# ProPrj___2025-12-12.net
KiCad netlist of a schematic drawn in EasyEDA Pro
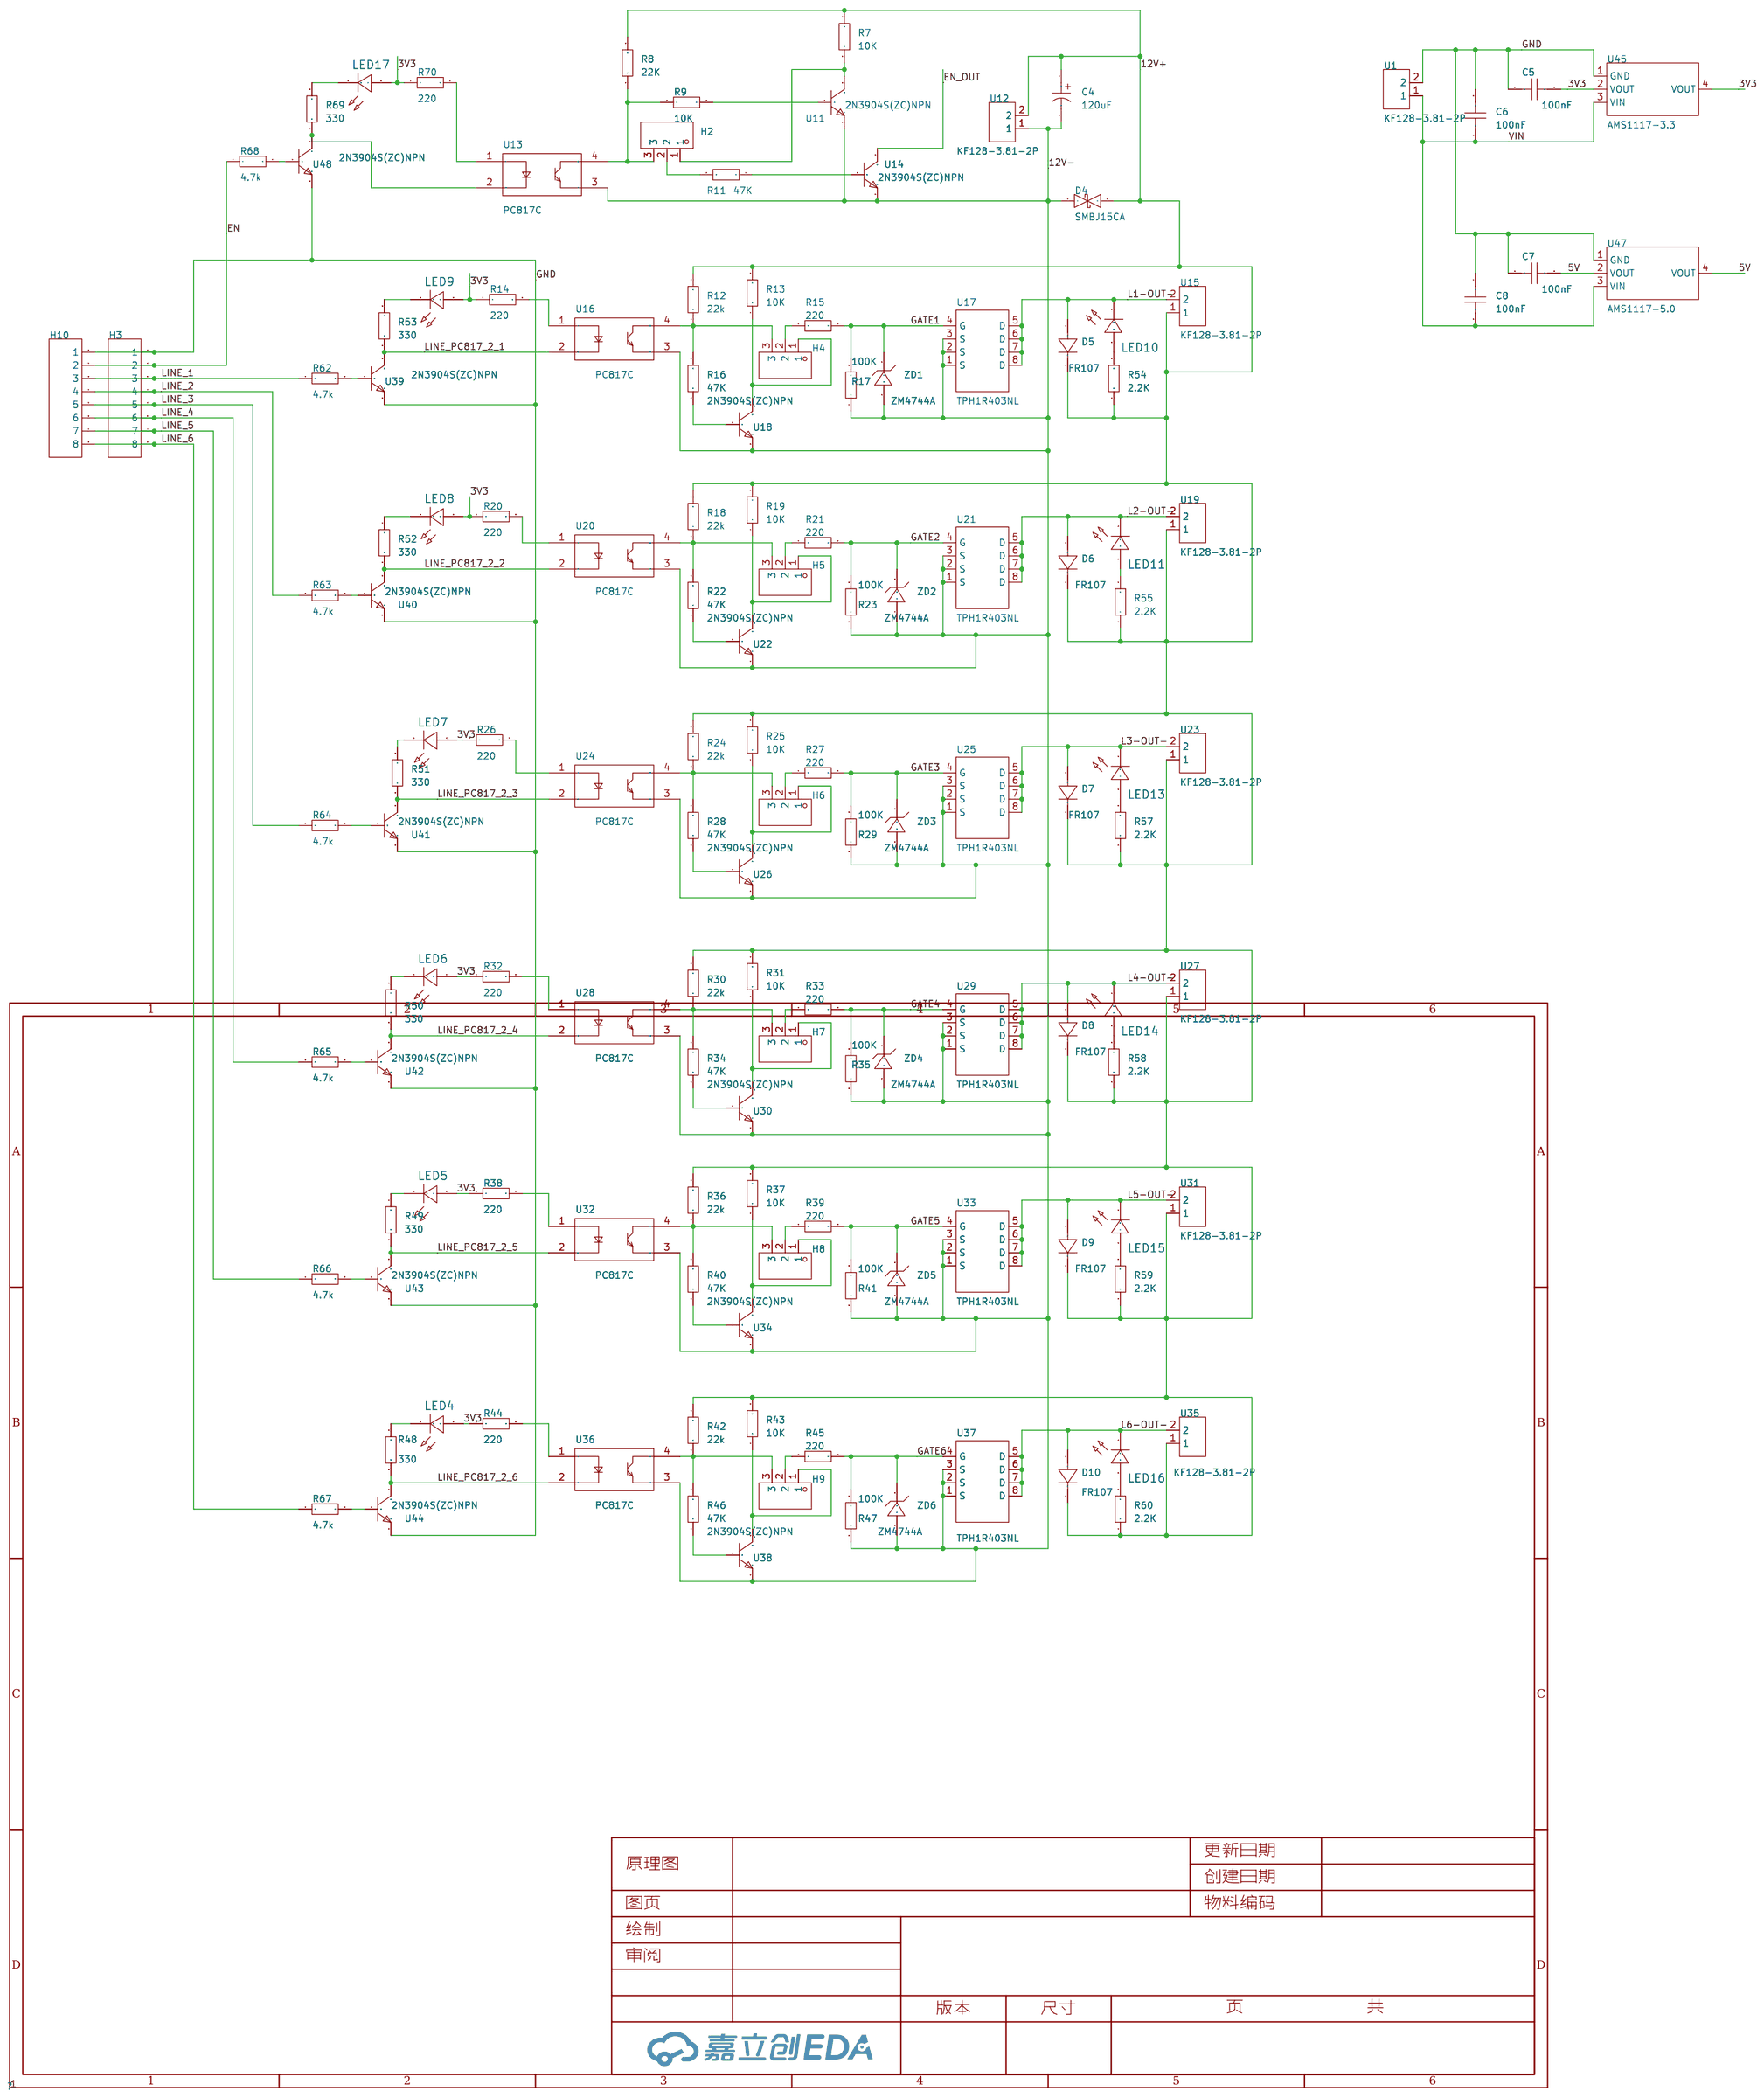
[diagram p0: 光耦隔离输出]
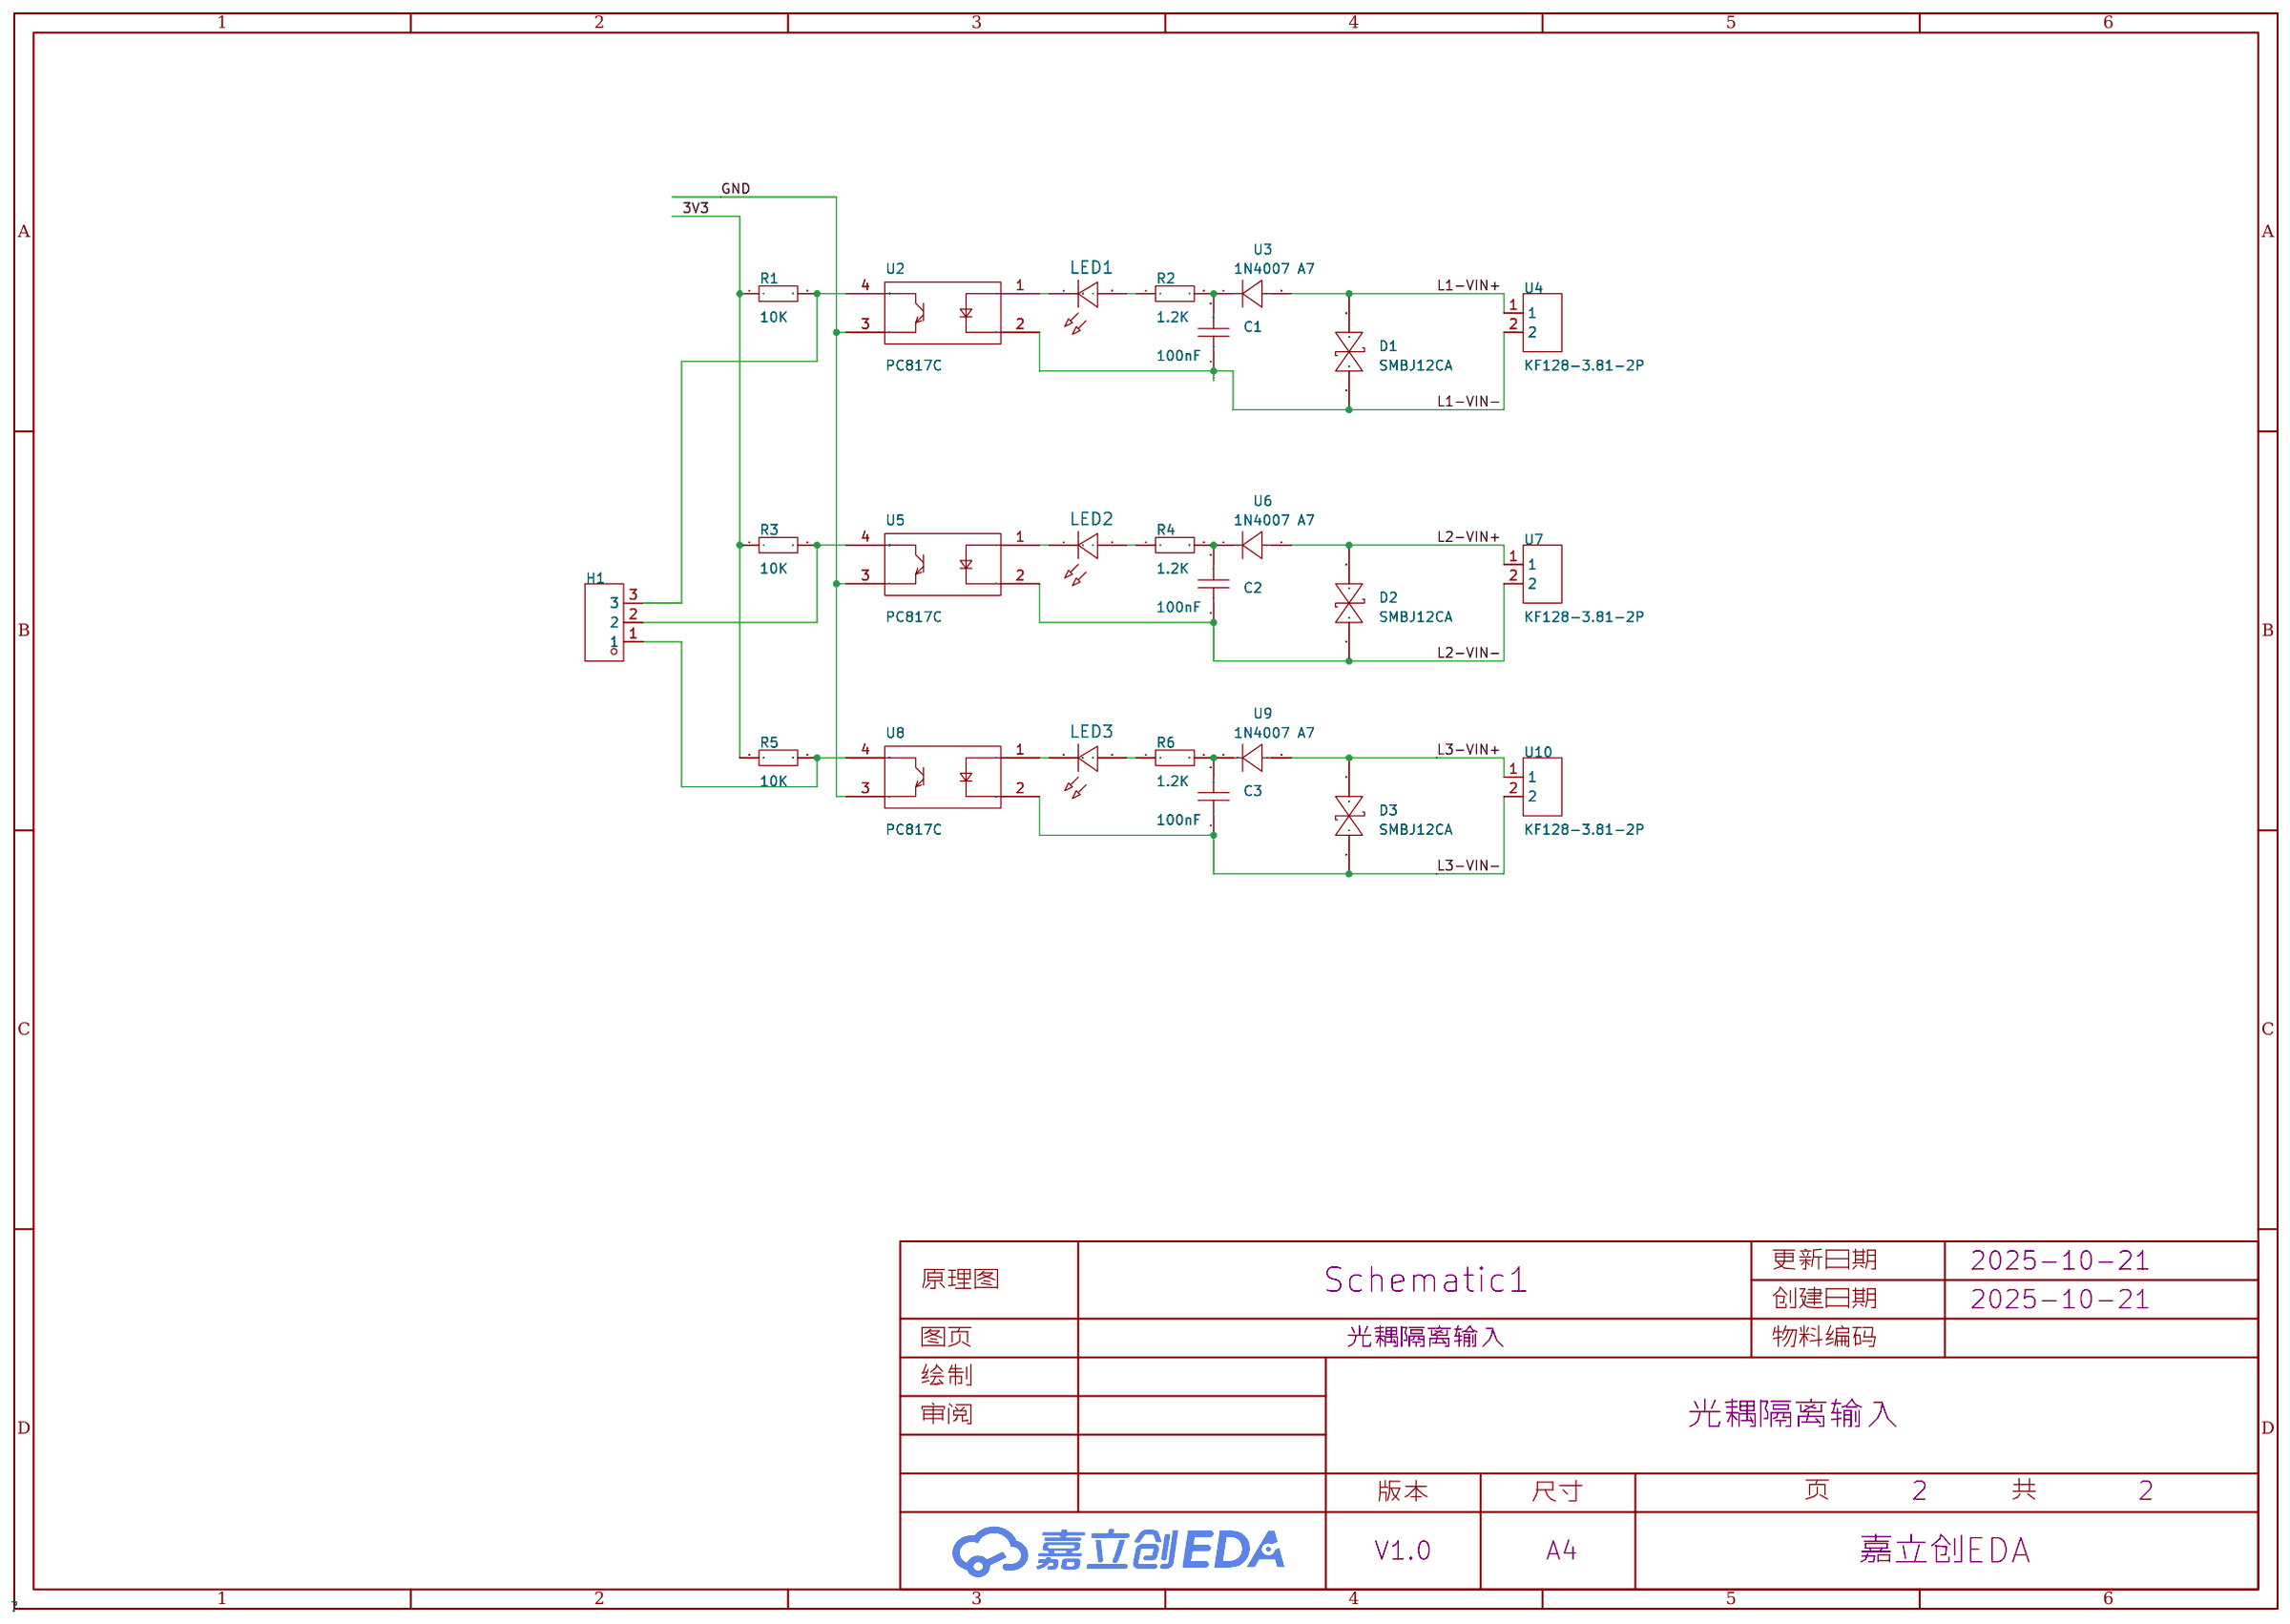
[diagram p1: 光耦隔离输入]

(export (version "E")
  (design (tool "Eeschema 10.0.6"))
  (components
    (comp (ref "C4")
      (value "120uF")
      (footprint "easyedapro:CAP-TH_BD6.3-P2.50-D0.5-FD")
      (description "容值:120uF;精度:±20%;额定电压:35V;纹波电流:550mA@100kHz;等效串联电阻(ESR):150mΩ@100kHz;")
      (fields
        (field (name "Manufacturer Part") "DHG035M127E090S1AA")
        (field (name "Manufacturer") "KNSCHA(科尼盛)")
      )
      (libsource (lib "easyedapro") (part "DHG035M127E090S1AA"))
    )
    (comp (ref "C5")
      (value "100nF")
      (footprint "easyedapro:C0603")
      (libsource (lib "easyedapro") (part "CapAcitance"))
    )
    (comp (ref "C6")
      (value "100nF")
      (footprint "easyedapro:C0603")
      (libsource (lib "easyedapro") (part "CapAcitance"))
    )
    (comp (ref "C7")
      (value "100nF")
      (footprint "easyedapro:C0603")
      (libsource (lib "easyedapro") (part "CapAcitance"))
    )
    (comp (ref "C8")
      (value "100nF")
      (footprint "easyedapro:C0603")
      (libsource (lib "easyedapro") (part "CapAcitance"))
    )
    (comp (ref "D4")
      (value "SMBJ15CA")
      (footprint "easyedapro:SMB_L4.6-W3.6-LS5.3-BI")
      (description "反向截止电压(Vrwm):15V;钳位电压:24.4V;峰值脉冲电流(Ipp):24.6A;击穿电压:16.7V;")
      (fields (field (name "Manufacturer") "JJW(捷捷微)"))
      (libsource (lib "easyedapro") (part "SMBJ15CA_C330064"))
    )
    (comp (ref "D5")
      (value "FR107")
      (footprint "easyedapro:SOD-123_L2.8-W1.8-LS3.7-RD")
      (description "二极管配置:-;正向压降(Vf):1.3V@1A;直流反向耐压(Vr):1kV;整流电流:1A;反向恢复时间(Trr):500ns;")
      (fields (field (name "Manufacturer") "JSMSEMI(杰盛微)"))
      (libsource (lib "easyedapro") (part "FR107_C963379"))
    )
    (comp (ref "D6")
      (value "FR107")
      (footprint "easyedapro:SOD-123_L2.8-W1.8-LS3.7-RD")
      (description "二极管配置:-;正向压降(Vf):1.3V@1A;直流反向耐压(Vr):1kV;整流电流:1A;反向恢复时间(Trr):500ns;")
      (fields (field (name "Manufacturer") "JSMSEMI(杰盛微)"))
      (libsource (lib "easyedapro") (part "FR107_C963379"))
    )
    (comp (ref "D7")
      (value "FR107")
      (footprint "easyedapro:SOD-123_L2.8-W1.8-LS3.7-RD")
      (description "二极管配置:-;正向压降(Vf):1.3V@1A;直流反向耐压(Vr):1kV;整流电流:1A;反向恢复时间(Trr):500ns;")
      (fields (field (name "Manufacturer") "JSMSEMI(杰盛微)"))
      (libsource (lib "easyedapro") (part "FR107_C963379"))
    )
    (comp (ref "D8")
      (value "FR107")
      (footprint "easyedapro:SOD-123_L2.8-W1.8-LS3.7-RD")
      (description "二极管配置:-;正向压降(Vf):1.3V@1A;直流反向耐压(Vr):1kV;整流电流:1A;反向恢复时间(Trr):500ns;")
      (fields (field (name "Manufacturer") "JSMSEMI(杰盛微)"))
      (libsource (lib "easyedapro") (part "FR107_C963379"))
    )
    (comp (ref "D9")
      (value "FR107")
      (footprint "easyedapro:SOD-123_L2.8-W1.8-LS3.7-RD")
      (description "二极管配置:-;正向压降(Vf):1.3V@1A;直流反向耐压(Vr):1kV;整流电流:1A;反向恢复时间(Trr):500ns;")
      (fields (field (name "Manufacturer") "JSMSEMI(杰盛微)"))
      (libsource (lib "easyedapro") (part "FR107_C963379"))
    )
    (comp (ref "D10")
      (value "FR107")
      (footprint "easyedapro:SOD-123_L2.8-W1.8-LS3.7-RD")
      (description "二极管配置:-;正向压降(Vf):1.3V@1A;直流反向耐压(Vr):1kV;整流电流:1A;反向恢复时间(Trr):500ns;")
      (fields (field (name "Manufacturer") "JSMSEMI(杰盛微)"))
      (libsource (lib "easyedapro") (part "FR107_C963379"))
    )
    (comp (ref "H2")
      (value "~")
      (footprint "easyedapro:HDR-TH_3P-P2.54-V-M")
      (libsource (lib "easyedapro") (part "HDR-M_2.54_1x3P"))
    )
    (comp (ref "H3")
      (value "~")
      (footprint "easyedapro:HDR-TH_8P-P2.54-V-M")
      (libsource (lib "easyedapro") (part "Header-Male-2.54_1x8"))
    )
    (comp (ref "H4")
      (value "~")
      (footprint "easyedapro:HDR-TH_3P-P2.54-V-M")
      (libsource (lib "easyedapro") (part "HDR-M_2.54_1x3P"))
    )
    (comp (ref "H5")
      (value "~")
      (footprint "easyedapro:HDR-TH_3P-P2.54-V-M")
      (libsource (lib "easyedapro") (part "HDR-M_2.54_1x3P"))
    )
    (comp (ref "H6")
      (value "~")
      (footprint "easyedapro:HDR-TH_3P-P2.54-V-M")
      (libsource (lib "easyedapro") (part "HDR-M_2.54_1x3P"))
    )
    (comp (ref "H7")
      (value "~")
      (footprint "easyedapro:HDR-TH_3P-P2.54-V-M")
      (libsource (lib "easyedapro") (part "HDR-M_2.54_1x3P"))
    )
    (comp (ref "H8")
      (value "~")
      (footprint "easyedapro:HDR-TH_3P-P2.54-V-M")
      (libsource (lib "easyedapro") (part "HDR-M_2.54_1x3P"))
    )
    (comp (ref "H9")
      (value "~")
      (footprint "easyedapro:HDR-TH_3P-P2.54-V-M")
      (libsource (lib "easyedapro") (part "HDR-M_2.54_1x3P"))
    )
    (comp (ref "H10")
      (value "~")
      (footprint "easyedapro:HDR-TH_8P-P2.54-V-M")
      (libsource (lib "easyedapro") (part "Header-Male-2.54_1x8"))
    )
    (comp (ref "LED4")
      (value "~")
      (footprint "easyedapro:LED_0603")
      (libsource (lib "easyedapro") (part "LED_R"))
    )
    (comp (ref "LED5")
      (value "~")
      (footprint "easyedapro:LED_0603")
      (libsource (lib "easyedapro") (part "LED_R"))
    )
    (comp (ref "LED6")
      (value "~")
      (footprint "easyedapro:LED_0603")
      (libsource (lib "easyedapro") (part "LED_R"))
    )
    (comp (ref "LED7")
      (value "~")
      (footprint "easyedapro:LED_0603")
      (libsource (lib "easyedapro") (part "LED_R"))
    )
    (comp (ref "LED8")
      (value "~")
      (footprint "easyedapro:LED_0603")
      (libsource (lib "easyedapro") (part "LED_R"))
    )
    (comp (ref "LED9")
      (value "~")
      (footprint "easyedapro:LED_0603")
      (libsource (lib "easyedapro") (part "LED_R"))
    )
    (comp (ref "LED10")
      (value "~")
      (footprint "easyedapro:LED_0603")
      (libsource (lib "easyedapro") (part "LED_R"))
    )
    (comp (ref "LED11")
      (value "~")
      (footprint "easyedapro:LED_0603")
      (libsource (lib "easyedapro") (part "LED_R"))
    )
    (comp (ref "LED13")
      (value "~")
      (footprint "easyedapro:LED_0603")
      (libsource (lib "easyedapro") (part "LED_R"))
    )
    (comp (ref "LED14")
      (value "~")
      (footprint "easyedapro:LED_0603")
      (libsource (lib "easyedapro") (part "LED_R"))
    )
    (comp (ref "LED15")
      (value "~")
      (footprint "easyedapro:LED_0603")
      (libsource (lib "easyedapro") (part "LED_R"))
    )
    (comp (ref "LED16")
      (value "~")
      (footprint "easyedapro:LED_0603")
      (libsource (lib "easyedapro") (part "LED_R"))
    )
    (comp (ref "LED17")
      (value "~")
      (footprint "easyedapro:LED_0603")
      (libsource (lib "easyedapro") (part "LED_R"))
    )
    (comp (ref "R7") (value "10K") (footprint "easyedapro:R0603") (libsource (lib "easyedapro") (part "电阻")))
    (comp (ref "R8") (value "22K") (footprint "easyedapro:R0603") (libsource (lib "easyedapro") (part "电阻")))
    (comp (ref "R9") (value "10K") (footprint "easyedapro:R0603") (libsource (lib "easyedapro") (part "电阻")))
    (comp (ref "R11") (value "47K") (footprint "easyedapro:R0603") (libsource (lib "easyedapro") (part "电阻")))
    (comp (ref "R12") (value "22k") (footprint "easyedapro:R0603") (libsource (lib "easyedapro") (part "电阻")))
    (comp (ref "R13") (value "10K") (footprint "easyedapro:R0603") (libsource (lib "easyedapro") (part "电阻")))
    (comp (ref "R14") (value "220") (footprint "easyedapro:R0603") (libsource (lib "easyedapro") (part "电阻")))
    (comp (ref "R15") (value "220") (footprint "easyedapro:R0603") (libsource (lib "easyedapro") (part "电阻")))
    (comp (ref "R16") (value "47K") (footprint "easyedapro:R0603") (libsource (lib "easyedapro") (part "电阻")))
    (comp (ref "R17")
      (value "100K")
      (footprint "easyedapro:R0603")
      (libsource (lib "easyedapro") (part "电阻"))
    )
    (comp (ref "R18") (value "22k") (footprint "easyedapro:R0603") (libsource (lib "easyedapro") (part "电阻")))
    (comp (ref "R19") (value "10K") (footprint "easyedapro:R0603") (libsource (lib "easyedapro") (part "电阻")))
    (comp (ref "R20") (value "220") (footprint "easyedapro:R0603") (libsource (lib "easyedapro") (part "电阻")))
    (comp (ref "R21") (value "220") (footprint "easyedapro:R0603") (libsource (lib "easyedapro") (part "电阻")))
    (comp (ref "R22") (value "47K") (footprint "easyedapro:R0603") (libsource (lib "easyedapro") (part "电阻")))
    (comp (ref "R23")
      (value "100K")
      (footprint "easyedapro:R0603")
      (libsource (lib "easyedapro") (part "电阻"))
    )
    (comp (ref "R24") (value "22k") (footprint "easyedapro:R0603") (libsource (lib "easyedapro") (part "电阻")))
    (comp (ref "R25") (value "10K") (footprint "easyedapro:R0603") (libsource (lib "easyedapro") (part "电阻")))
    (comp (ref "R26") (value "220") (footprint "easyedapro:R0603") (libsource (lib "easyedapro") (part "电阻")))
    (comp (ref "R27") (value "220") (footprint "easyedapro:R0603") (libsource (lib "easyedapro") (part "电阻")))
    (comp (ref "R28") (value "47K") (footprint "easyedapro:R0603") (libsource (lib "easyedapro") (part "电阻")))
    (comp (ref "R29")
      (value "100K")
      (footprint "easyedapro:R0603")
      (libsource (lib "easyedapro") (part "电阻"))
    )
    (comp (ref "R30") (value "22k") (footprint "easyedapro:R0603") (libsource (lib "easyedapro") (part "电阻")))
    (comp (ref "R31") (value "10K") (footprint "easyedapro:R0603") (libsource (lib "easyedapro") (part "电阻")))
    (comp (ref "R32") (value "220") (footprint "easyedapro:R0603") (libsource (lib "easyedapro") (part "电阻")))
    (comp (ref "R33") (value "220") (footprint "easyedapro:R0603") (libsource (lib "easyedapro") (part "电阻")))
    (comp (ref "R34") (value "47K") (footprint "easyedapro:R0603") (libsource (lib "easyedapro") (part "电阻")))
    (comp (ref "R35")
      (value "100K")
      (footprint "easyedapro:R0603")
      (libsource (lib "easyedapro") (part "电阻"))
    )
    (comp (ref "R36") (value "22k") (footprint "easyedapro:R0603") (libsource (lib "easyedapro") (part "电阻")))
    (comp (ref "R37") (value "10K") (footprint "easyedapro:R0603") (libsource (lib "easyedapro") (part "电阻")))
    (comp (ref "R38") (value "220") (footprint "easyedapro:R0603") (libsource (lib "easyedapro") (part "电阻")))
    (comp (ref "R39") (value "220") (footprint "easyedapro:R0603") (libsource (lib "easyedapro") (part "电阻")))
    (comp (ref "R40") (value "47K") (footprint "easyedapro:R0603") (libsource (lib "easyedapro") (part "电阻")))
    (comp (ref "R41")
      (value "100K")
      (footprint "easyedapro:R0603")
      (libsource (lib "easyedapro") (part "电阻"))
    )
    (comp (ref "R42") (value "22k") (footprint "easyedapro:R0603") (libsource (lib "easyedapro") (part "电阻")))
    (comp (ref "R43") (value "10K") (footprint "easyedapro:R0603") (libsource (lib "easyedapro") (part "电阻")))
    (comp (ref "R44") (value "220") (footprint "easyedapro:R0603") (libsource (lib "easyedapro") (part "电阻")))
    (comp (ref "R45") (value "220") (footprint "easyedapro:R0603") (libsource (lib "easyedapro") (part "电阻")))
    (comp (ref "R46") (value "47K") (footprint "easyedapro:R0603") (libsource (lib "easyedapro") (part "电阻")))
    (comp (ref "R47")
      (value "100K")
      (footprint "easyedapro:R0603")
      (libsource (lib "easyedapro") (part "电阻"))
    )
    (comp (ref "R48") (value "330") (footprint "easyedapro:R0603") (libsource (lib "easyedapro") (part "电阻")))
    (comp (ref "R49") (value "330") (footprint "easyedapro:R0603") (libsource (lib "easyedapro") (part "电阻")))
    (comp (ref "R50") (value "330") (footprint "easyedapro:R0603") (libsource (lib "easyedapro") (part "电阻")))
    (comp (ref "R51") (value "330") (footprint "easyedapro:R0603") (libsource (lib "easyedapro") (part "电阻")))
    (comp (ref "R52") (value "330") (footprint "easyedapro:R0603") (libsource (lib "easyedapro") (part "电阻")))
    (comp (ref "R53") (value "330") (footprint "easyedapro:R0603") (libsource (lib "easyedapro") (part "电阻")))
    (comp (ref "R54")
      (value "2.2K")
      (footprint "easyedapro:R0603")
      (libsource (lib "easyedapro") (part "电阻"))
    )
    (comp (ref "R55")
      (value "2.2K")
      (footprint "easyedapro:R0603")
      (libsource (lib "easyedapro") (part "电阻"))
    )
    (comp (ref "R57")
      (value "2.2K")
      (footprint "easyedapro:R0603")
      (libsource (lib "easyedapro") (part "电阻"))
    )
    (comp (ref "R58")
      (value "2.2K")
      (footprint "easyedapro:R0603")
      (libsource (lib "easyedapro") (part "电阻"))
    )
    (comp (ref "R59")
      (value "2.2K")
      (footprint "easyedapro:R0603")
      (libsource (lib "easyedapro") (part "电阻"))
    )
    (comp (ref "R60")
      (value "2.2K")
      (footprint "easyedapro:R0603")
      (libsource (lib "easyedapro") (part "电阻"))
    )
    (comp (ref "R62")
      (value "4.7k")
      (footprint "easyedapro:R0603")
      (libsource (lib "easyedapro") (part "电阻"))
    )
    (comp (ref "R63")
      (value "4.7k")
      (footprint "easyedapro:R0603")
      (libsource (lib "easyedapro") (part "电阻"))
    )
    (comp (ref "R64")
      (value "4.7k")
      (footprint "easyedapro:R0603")
      (libsource (lib "easyedapro") (part "电阻"))
    )
    (comp (ref "R65")
      (value "4.7k")
      (footprint "easyedapro:R0603")
      (libsource (lib "easyedapro") (part "电阻"))
    )
    (comp (ref "R66")
      (value "4.7k")
      (footprint "easyedapro:R0603")
      (libsource (lib "easyedapro") (part "电阻"))
    )
    (comp (ref "R67")
      (value "4.7k")
      (footprint "easyedapro:R0603")
      (libsource (lib "easyedapro") (part "电阻"))
    )
    (comp (ref "R68")
      (value "4.7k")
      (footprint "easyedapro:R0603")
      (libsource (lib "easyedapro") (part "电阻"))
    )
    (comp (ref "R69") (value "330") (footprint "easyedapro:R0603") (libsource (lib "easyedapro") (part "电阻")))
    (comp (ref "R70") (value "220") (footprint "easyedapro:R0603") (libsource (lib "easyedapro") (part "电阻")))
    (comp (ref "U1")
      (value "KF128-3.81-2P")
      (footprint "easyedapro:CONN-TH_2P-P3.81_KF128-3.81-2P")
      (libsource (lib "easyedapro") (part "KF128-3.81-2P_C9900030554"))
    )
    (comp (ref "U11")
      (value "2N3904S(ZC)NPN")
      (footprint "easyedapro:SOT-23-3_L2.9-W1.3-P0.95-LS2.4-BR")
      (libsource (lib "easyedapro") (part "2N3904S(ZC)NPN"))
    )
    (comp (ref "U12")
      (value "KF128-3.81-2P")
      (footprint "easyedapro:CONN-TH_2P-P3.81_KF128-3.81-2P")
      (libsource (lib "easyedapro") (part "KF128-3.81-2P_C9900030554"))
    )
    (comp (ref "U13")
      (value "PC817C")
      (footprint "easyedapro:DIP-4_L4.6-W6.5-P2.54-LS7.6-BL")
      (fields (field (name "Manufacturer") "GOODWORK(固得沃克)"))
      (libsource (lib "easyedapro") (part "PC817-4"))
    )
    (comp (ref "U14")
      (value "2N3904S(ZC)NPN")
      (footprint "easyedapro:SOT-23-3_L2.9-W1.3-P0.95-LS2.4-BR")
      (libsource (lib "easyedapro") (part "2N3904S(ZC)NPN"))
    )
    (comp (ref "U15")
      (value "KF128-3.81-2P")
      (footprint "easyedapro:CONN-TH_2P-P3.81_KF128-3.81-2P")
      (libsource (lib "easyedapro") (part "KF128-3.81-2P_C9900030554"))
    )
    (comp (ref "U16")
      (value "PC817C")
      (footprint "easyedapro:DIP-4_L4.6-W6.5-P2.54-LS7.6-BL")
      (fields (field (name "Manufacturer") "GOODWORK(固得沃克)"))
      (libsource (lib "easyedapro") (part "PC817-4"))
    )
    (comp (ref "U17")
      (value "TPH1R403NL")
      (footprint "easyedapro:DFN-8_L5.0-W5.0-P1.27-LS6.0-EP")
      (libsource (lib "easyedapro") (part "TPH1R403NL_C9900016373"))
    )
    (comp (ref "U18")
      (value "2N3904S(ZC)NPN")
      (footprint "easyedapro:SOT-23-3_L2.9-W1.3-P0.95-LS2.4-BR")
      (libsource (lib "easyedapro") (part "2N3904S(ZC)NPN"))
    )
    (comp (ref "U19")
      (value "KF128-3.81-2P")
      (footprint "easyedapro:CONN-TH_2P-P3.81_KF128-3.81-2P")
      (libsource (lib "easyedapro") (part "KF128-3.81-2P_C9900030554"))
    )
    (comp (ref "U20")
      (value "PC817C")
      (footprint "easyedapro:DIP-4_L4.6-W6.5-P2.54-LS7.6-BL")
      (fields (field (name "Manufacturer") "GOODWORK(固得沃克)"))
      (libsource (lib "easyedapro") (part "PC817-4"))
    )
    (comp (ref "U21")
      (value "TPH1R403NL")
      (footprint "easyedapro:DFN-8_L5.0-W5.0-P1.27-LS6.0-EP")
      (libsource (lib "easyedapro") (part "TPH1R403NL_C9900016373"))
    )
    (comp (ref "U22")
      (value "2N3904S(ZC)NPN")
      (footprint "easyedapro:SOT-23-3_L2.9-W1.3-P0.95-LS2.4-BR")
      (libsource (lib "easyedapro") (part "2N3904S(ZC)NPN"))
    )
    (comp (ref "U23")
      (value "KF128-3.81-2P")
      (footprint "easyedapro:CONN-TH_2P-P3.81_KF128-3.81-2P")
      (libsource (lib "easyedapro") (part "KF128-3.81-2P_C9900030554"))
    )
    (comp (ref "U24")
      (value "PC817C")
      (footprint "easyedapro:DIP-4_L4.6-W6.5-P2.54-LS7.6-BL")
      (fields (field (name "Manufacturer") "GOODWORK(固得沃克)"))
      (libsource (lib "easyedapro") (part "PC817-4"))
    )
    (comp (ref "U25")
      (value "TPH1R403NL")
      (footprint "easyedapro:DFN-8_L5.0-W5.0-P1.27-LS6.0-EP")
      (libsource (lib "easyedapro") (part "TPH1R403NL_C9900016373"))
    )
    (comp (ref "U26")
      (value "2N3904S(ZC)NPN")
      (footprint "easyedapro:SOT-23-3_L2.9-W1.3-P0.95-LS2.4-BR")
      (libsource (lib "easyedapro") (part "2N3904S(ZC)NPN"))
    )
    (comp (ref "U27")
      (value "KF128-3.81-2P")
      (footprint "easyedapro:CONN-TH_2P-P3.81_KF128-3.81-2P")
      (libsource (lib "easyedapro") (part "KF128-3.81-2P_C9900030554"))
    )
    (comp (ref "U28")
      (value "PC817C")
      (footprint "easyedapro:DIP-4_L4.6-W6.5-P2.54-LS7.6-BL")
      (fields (field (name "Manufacturer") "GOODWORK(固得沃克)"))
      (libsource (lib "easyedapro") (part "PC817-4"))
    )
    (comp (ref "U29")
      (value "TPH1R403NL")
      (footprint "easyedapro:DFN-8_L5.0-W5.0-P1.27-LS6.0-EP")
      (libsource (lib "easyedapro") (part "TPH1R403NL_C9900016373"))
    )
    (comp (ref "U30")
      (value "2N3904S(ZC)NPN")
      (footprint "easyedapro:SOT-23-3_L2.9-W1.3-P0.95-LS2.4-BR")
      (libsource (lib "easyedapro") (part "2N3904S(ZC)NPN"))
    )
    (comp (ref "U31")
      (value "KF128-3.81-2P")
      (footprint "easyedapro:CONN-TH_2P-P3.81_KF128-3.81-2P")
      (libsource (lib "easyedapro") (part "KF128-3.81-2P_C9900030554"))
    )
    (comp (ref "U32")
      (value "PC817C")
      (footprint "easyedapro:DIP-4_L4.6-W6.5-P2.54-LS7.6-BL")
      (fields (field (name "Manufacturer") "GOODWORK(固得沃克)"))
      (libsource (lib "easyedapro") (part "PC817-4"))
    )
    (comp (ref "U33")
      (value "TPH1R403NL")
      (footprint "easyedapro:DFN-8_L5.0-W5.0-P1.27-LS6.0-EP")
      (libsource (lib "easyedapro") (part "TPH1R403NL_C9900016373"))
    )
    (comp (ref "U34")
      (value "2N3904S(ZC)NPN")
      (footprint "easyedapro:SOT-23-3_L2.9-W1.3-P0.95-LS2.4-BR")
      (libsource (lib "easyedapro") (part "2N3904S(ZC)NPN"))
    )
    (comp (ref "U35")
      (value "KF128-3.81-2P")
      (footprint "easyedapro:CONN-TH_2P-P3.81_KF128-3.81-2P")
      (libsource (lib "easyedapro") (part "KF128-3.81-2P_C9900030554"))
    )
    (comp (ref "U36")
      (value "PC817C")
      (footprint "easyedapro:DIP-4_L4.6-W6.5-P2.54-LS7.6-BL")
      (fields (field (name "Manufacturer") "GOODWORK(固得沃克)"))
      (libsource (lib "easyedapro") (part "PC817-4"))
    )
    (comp (ref "U37")
      (value "TPH1R403NL")
      (footprint "easyedapro:DFN-8_L5.0-W5.0-P1.27-LS6.0-EP")
      (libsource (lib "easyedapro") (part "TPH1R403NL_C9900016373"))
    )
    (comp (ref "U38")
      (value "2N3904S(ZC)NPN")
      (footprint "easyedapro:SOT-23-3_L2.9-W1.3-P0.95-LS2.4-BR")
      (libsource (lib "easyedapro") (part "2N3904S(ZC)NPN"))
    )
    (comp (ref "U39")
      (value "2N3904S(ZC)NPN")
      (footprint "easyedapro:SOT-23-3_L2.9-W1.3-P0.95-LS2.4-BR")
      (libsource (lib "easyedapro") (part "2N3904S(ZC)NPN"))
    )
    (comp (ref "U40")
      (value "2N3904S(ZC)NPN")
      (footprint "easyedapro:SOT-23-3_L2.9-W1.3-P0.95-LS2.4-BR")
      (libsource (lib "easyedapro") (part "2N3904S(ZC)NPN"))
    )
    (comp (ref "U41")
      (value "2N3904S(ZC)NPN")
      (footprint "easyedapro:SOT-23-3_L2.9-W1.3-P0.95-LS2.4-BR")
      (libsource (lib "easyedapro") (part "2N3904S(ZC)NPN"))
    )
    (comp (ref "U42")
      (value "2N3904S(ZC)NPN")
      (footprint "easyedapro:SOT-23-3_L2.9-W1.3-P0.95-LS2.4-BR")
      (libsource (lib "easyedapro") (part "2N3904S(ZC)NPN"))
    )
    (comp (ref "U43")
      (value "2N3904S(ZC)NPN")
      (footprint "easyedapro:SOT-23-3_L2.9-W1.3-P0.95-LS2.4-BR")
      (libsource (lib "easyedapro") (part "2N3904S(ZC)NPN"))
    )
    (comp (ref "U44")
      (value "2N3904S(ZC)NPN")
      (footprint "easyedapro:SOT-23-3_L2.9-W1.3-P0.95-LS2.4-BR")
      (libsource (lib "easyedapro") (part "2N3904S(ZC)NPN"))
    )
    (comp (ref "U45")
      (value "AMS1117-3.3")
      (footprint "easyedapro:SOT-223-3_L6.5-W3.4-P2.30-LS7.0-BR")
      (description "输出类型:固定;工作电压:16V;输出电压:3.3V;输出电流:1A;电源纹波抑制比(PSRR):72dB@(120Hz);输出极性:正极;")
      (fields (field (name "Manufacturer") "AMS"))
      (libsource (lib "easyedapro") (part "AMS1117-3.3"))
    )
    (comp (ref "U47")
      (value "AMS1117-5.0")
      (footprint "easyedapro:SOT-223_L6.5-W3.5-P2.30-LS7.0-BR")
      (description "输出类型:固定;工作电压:15V;输出电压:5V;输出电流:1A;电源纹波抑制比(PSRR):60dB;输出极性:正极;")
      (fields (field (name "Manufacturer") "AMS"))
      (libsource (lib "easyedapro") (part "AMS1117-5.0"))
    )
    (comp (ref "U48")
      (value "2N3904S(ZC)NPN")
      (footprint "easyedapro:SOT-23-3_L2.9-W1.3-P0.95-LS2.4-BR")
      (libsource (lib "easyedapro") (part "2N3904S(ZC)NPN"))
    )
    (comp (ref "ZD1")
      (value "ZM4744A")
      (footprint "easyedapro:LL-41_L5.0-W2.5-LS5.0-RD")
      (description "二极管配置:独立式;稳压值(标称值):15V;耗散功率(Pd):1W;")
      (fields (field (name "Manufacturer") "ST(先科)"))
      (libsource (lib "easyedapro") (part "ZM4744A"))
    )
    (comp (ref "ZD2")
      (value "ZM4744A")
      (footprint "easyedapro:LL-41_L5.0-W2.5-LS5.0-RD")
      (description "二极管配置:独立式;稳压值(标称值):15V;耗散功率(Pd):1W;")
      (fields (field (name "Manufacturer") "ST(先科)"))
      (libsource (lib "easyedapro") (part "ZM4744A"))
    )
    (comp (ref "ZD3")
      (value "ZM4744A")
      (footprint "easyedapro:LL-41_L5.0-W2.5-LS5.0-RD")
      (description "二极管配置:独立式;稳压值(标称值):15V;耗散功率(Pd):1W;")
      (fields (field (name "Manufacturer") "ST(先科)"))
      (libsource (lib "easyedapro") (part "ZM4744A"))
    )
    (comp (ref "ZD4")
      (value "ZM4744A")
      (footprint "easyedapro:LL-41_L5.0-W2.5-LS5.0-RD")
      (description "二极管配置:独立式;稳压值(标称值):15V;耗散功率(Pd):1W;")
      (fields (field (name "Manufacturer") "ST(先科)"))
      (libsource (lib "easyedapro") (part "ZM4744A"))
    )
    (comp (ref "ZD5")
      (value "ZM4744A")
      (footprint "easyedapro:LL-41_L5.0-W2.5-LS5.0-RD")
      (description "二极管配置:独立式;稳压值(标称值):15V;耗散功率(Pd):1W;")
      (fields (field (name "Manufacturer") "ST(先科)"))
      (libsource (lib "easyedapro") (part "ZM4744A"))
    )
    (comp (ref "ZD6")
      (value "ZM4744A")
      (footprint "easyedapro:LL-41_L5.0-W2.5-LS5.0-RD")
      (description "二极管配置:独立式;稳压值(标称值):15V;耗散功率(Pd):1W;")
      (fields (field (name "Manufacturer") "ST(先科)"))
      (libsource (lib "easyedapro") (part "ZM4744A"))
    )
    (comp (ref "C1")
      (value "100nF")
      (footprint "easyedapro:C0603")
      (libsource (lib "easyedapro") (part "CapAcitance"))
    )
    (comp (ref "C2")
      (value "100nF")
      (footprint "easyedapro:C0603")
      (libsource (lib "easyedapro") (part "CapAcitance"))
    )
    (comp (ref "C3")
      (value "100nF")
      (footprint "easyedapro:C0603")
      (libsource (lib "easyedapro") (part "CapAcitance"))
    )
    (comp (ref "D1")
      (value "SMBJ12CA")
      (footprint "easyedapro:SMB_L4.6-W3.6-LS5.3-BI")
      (description "反向截止电压(Vrwm):12V;最大钳位电压:19.9V;峰值脉冲电流(Ipp):30.2A;击穿电压:13.3V;")
      (fields (field (name "Manufacturer") "FMS(美丽微)"))
      (libsource (lib "easyedapro") (part "SMBJ12CA_C143145"))
    )
    (comp (ref "D2")
      (value "SMBJ12CA")
      (footprint "easyedapro:SMB_L4.6-W3.6-LS5.3-BI")
      (description "反向截止电压(Vrwm):12V;最大钳位电压:19.9V;峰值脉冲电流(Ipp):30.2A;击穿电压:13.3V;")
      (fields (field (name "Manufacturer") "FMS(美丽微)"))
      (libsource (lib "easyedapro") (part "SMBJ12CA_C143145"))
    )
    (comp (ref "D3")
      (value "SMBJ12CA")
      (footprint "easyedapro:SMB_L4.6-W3.6-LS5.3-BI")
      (description "反向截止电压(Vrwm):12V;最大钳位电压:19.9V;峰值脉冲电流(Ipp):30.2A;击穿电压:13.3V;")
      (fields (field (name "Manufacturer") "FMS(美丽微)"))
      (libsource (lib "easyedapro") (part "SMBJ12CA_C143145"))
    )
    (comp (ref "H1")
      (value "~")
      (footprint "easyedapro:HDR-TH_3P-P2.54-V-M")
      (libsource (lib "easyedapro") (part "HDR-M_2.54_1x3P"))
    )
    (comp (ref "LED1")
      (value "~")
      (footprint "easyedapro:LED_0603")
      (libsource (lib "easyedapro") (part "LED_R"))
    )
    (comp (ref "LED2")
      (value "~")
      (footprint "easyedapro:LED_0603")
      (libsource (lib "easyedapro") (part "LED_R"))
    )
    (comp (ref "LED3")
      (value "~")
      (footprint "easyedapro:LED_0603")
      (libsource (lib "easyedapro") (part "LED_R"))
    )
    (comp (ref "R1") (value "10K") (footprint "easyedapro:R0603") (libsource (lib "easyedapro") (part "电阻")))
    (comp (ref "R2") (value "1.2K") (footprint "easyedapro:R0603") (libsource (lib "easyedapro") (part "电阻")))
    (comp (ref "R3") (value "10K") (footprint "easyedapro:R0603") (libsource (lib "easyedapro") (part "电阻")))
    (comp (ref "R4") (value "1.2K") (footprint "easyedapro:R0603") (libsource (lib "easyedapro") (part "电阻")))
    (comp (ref "R5") (value "10K") (footprint "easyedapro:R0603") (libsource (lib "easyedapro") (part "电阻")))
    (comp (ref "R6") (value "1.2K") (footprint "easyedapro:R0603") (libsource (lib "easyedapro") (part "电阻")))
    (comp (ref "U2")
      (value "PC817C")
      (footprint "easyedapro:DIP-4_L4.6-W6.5-P2.54-LS7.6-BL")
      (fields (field (name "Manufacturer") "GOODWORK(固得沃克)"))
      (libsource (lib "easyedapro") (part "PC817-4"))
    )
    (comp (ref "U3")
      (value "1N4007 A7")
      (footprint "easyedapro:SMA_L4.3-W2.6-LS5.1-RD")
      (fields (field (name "Manufacturer") "TWGMC(台湾迪嘉)"))
      (libsource (lib "easyedapro") (part "1N4007_C9900004759"))
    )
    (comp (ref "U4")
      (value "KF128-3.81-2P")
      (footprint "easyedapro:CONN-TH_2P-P3.81_KF128-3.81-2P")
      (libsource (lib "easyedapro") (part "KF128-3.81-2P_C9900030554"))
    )
    (comp (ref "U5")
      (value "PC817C")
      (footprint "easyedapro:DIP-4_L4.6-W6.5-P2.54-LS7.6-BL")
      (fields (field (name "Manufacturer") "GOODWORK(固得沃克)"))
      (libsource (lib "easyedapro") (part "PC817-4"))
    )
    (comp (ref "U6")
      (value "1N4007 A7")
      (footprint "easyedapro:SMA_L4.3-W2.6-LS5.1-RD")
      (fields (field (name "Manufacturer") "TWGMC(台湾迪嘉)"))
      (libsource (lib "easyedapro") (part "1N4007_C9900004759"))
    )
    (comp (ref "U7")
      (value "KF128-3.81-2P")
      (footprint "easyedapro:CONN-TH_2P-P3.81_KF128-3.81-2P")
      (libsource (lib "easyedapro") (part "KF128-3.81-2P_C9900030554"))
    )
    (comp (ref "U8")
      (value "PC817C")
      (footprint "easyedapro:DIP-4_L4.6-W6.5-P2.54-LS7.6-BL")
      (fields (field (name "Manufacturer") "GOODWORK(固得沃克)"))
      (libsource (lib "easyedapro") (part "PC817-4"))
    )
    (comp (ref "U9")
      (value "1N4007 A7")
      (footprint "easyedapro:SMA_L4.3-W2.6-LS5.1-RD")
      (fields (field (name "Manufacturer") "TWGMC(台湾迪嘉)"))
      (libsource (lib "easyedapro") (part "1N4007_C9900004759"))
    )
    (comp (ref "U10")
      (value "KF128-3.81-2P")
      (footprint "easyedapro:CONN-TH_2P-P3.81_KF128-3.81-2P")
      (libsource (lib "easyedapro") (part "KF128-3.81-2P_C9900030554"))
    )
  )
  (nets
    (net (code "1") (name "3V3") (class "Default")
      (node (ref "C5") (pin "2") (pinfunction "2_2") (pintype "input"))
      (node (ref "LED17") (pin "2") (pinfunction "A_2") (pintype "input"))
      (node (ref "LED4") (pin "2") (pinfunction "A_2") (pintype "input"))
      (node (ref "LED5") (pin "2") (pinfunction "A_2") (pintype "input"))
      (node (ref "LED6") (pin "2") (pinfunction "A_2") (pintype "input"))
      (node (ref "LED7") (pin "2") (pinfunction "A_2") (pintype "input"))
      (node (ref "LED8") (pin "2") (pinfunction "A_2") (pintype "input"))
      (node (ref "LED9") (pin "2") (pinfunction "A_2") (pintype "input"))
      (node (ref "R1") (pin "1") (pinfunction "1_1") (pintype "input"))
      (node (ref "R14") (pin "1") (pinfunction "1_1") (pintype "input"))
      (node (ref "R20") (pin "1") (pinfunction "1_1") (pintype "input"))
      (node (ref "R26") (pin "1") (pinfunction "1_1") (pintype "input"))
      (node (ref "R3") (pin "1") (pinfunction "1_1") (pintype "input"))
      (node (ref "R32") (pin "1") (pinfunction "1_1") (pintype "input"))
      (node (ref "R38") (pin "1") (pinfunction "1_1") (pintype "input"))
      (node (ref "R44") (pin "1") (pinfunction "1_1") (pintype "input"))
      (node (ref "R5") (pin "1") (pinfunction "1_1") (pintype "input"))
      (node (ref "R70") (pin "1") (pinfunction "1_1") (pintype "input"))
      (node (ref "U45") (pin "2") (pinfunction "VOUT_2") (pintype "unspecified"))
      (node (ref "U45") (pin "4") (pinfunction "VOUT_4") (pintype "unspecified"))
    )
    (net (code "2") (name "5V") (class "Default")
      (node (ref "C7") (pin "2") (pinfunction "2_2") (pintype "input"))
      (node (ref "U47") (pin "2") (pinfunction "VOUT_2") (pintype "unspecified"))
      (node (ref "U47") (pin "4") (pinfunction "VOUT_4") (pintype "unspecified"))
    )
    (net (code "3") (name "12V+") (class "Default")
      (node (ref "C4") (pin "1") (pinfunction "1_1") (pintype "input"))
      (node (ref "D10") (pin "1") (pinfunction "C_1") (pintype "unspecified"))
      (node (ref "D4") (pin "2") (pinfunction "A_2") (pintype "input"))
      (node (ref "D5") (pin "1") (pinfunction "C_1") (pintype "unspecified"))
      (node (ref "D6") (pin "1") (pinfunction "C_1") (pintype "unspecified"))
      (node (ref "D7") (pin "1") (pinfunction "C_1") (pintype "unspecified"))
      (node (ref "D8") (pin "1") (pinfunction "C_1") (pintype "unspecified"))
      (node (ref "D9") (pin "1") (pinfunction "C_1") (pintype "unspecified"))
      (node (ref "R12") (pin "2") (pinfunction "2_2") (pintype "input"))
      (node (ref "R13") (pin "2") (pinfunction "2_2") (pintype "input"))
      (node (ref "R18") (pin "2") (pinfunction "2_2") (pintype "input"))
      (node (ref "R19") (pin "2") (pinfunction "2_2") (pintype "input"))
      (node (ref "R24") (pin "2") (pinfunction "2_2") (pintype "input"))
      (node (ref "R25") (pin "2") (pinfunction "2_2") (pintype "input"))
      (node (ref "R30") (pin "2") (pinfunction "2_2") (pintype "input"))
      (node (ref "R31") (pin "2") (pinfunction "2_2") (pintype "input"))
      (node (ref "R36") (pin "2") (pinfunction "2_2") (pintype "input"))
      (node (ref "R37") (pin "2") (pinfunction "2_2") (pintype "input"))
      (node (ref "R42") (pin "2") (pinfunction "2_2") (pintype "input"))
      (node (ref "R43") (pin "2") (pinfunction "2_2") (pintype "input"))
      (node (ref "R54") (pin "1") (pinfunction "1_1") (pintype "input"))
      (node (ref "R55") (pin "1") (pinfunction "1_1") (pintype "input"))
      (node (ref "R57") (pin "1") (pinfunction "1_1") (pintype "input"))
      (node (ref "R58") (pin "1") (pinfunction "1_1") (pintype "input"))
      (node (ref "R59") (pin "1") (pinfunction "1_1") (pintype "input"))
      (node (ref "R60") (pin "1") (pinfunction "1_1") (pintype "input"))
      (node (ref "R7") (pin "2") (pinfunction "2_2") (pintype "input"))
      (node (ref "R8") (pin "2") (pinfunction "2_2") (pintype "input"))
      (node (ref "U12") (pin "2") (pinfunction "2_2") (pintype "unspecified"))
      (node (ref "U15") (pin "1") (pinfunction "1_1") (pintype "unspecified"))
      (node (ref "U19") (pin "1") (pinfunction "1_1") (pintype "unspecified"))
      (node (ref "U23") (pin "1") (pinfunction "1_1") (pintype "unspecified"))
      (node (ref "U27") (pin "1") (pinfunction "1_1") (pintype "unspecified"))
      (node (ref "U31") (pin "1") (pinfunction "1_1") (pintype "unspecified"))
      (node (ref "U35") (pin "1") (pinfunction "1_1") (pintype "unspecified"))
    )
    (net (code "4") (name "12V-") (class "Default")
      (node (ref "C4") (pin "2") (pinfunction "2_2") (pintype "input"))
      (node (ref "D4") (pin "1") (pinfunction "K_1") (pintype "input"))
      (node (ref "R17") (pin "1") (pinfunction "1_1") (pintype "input"))
      (node (ref "R23") (pin "1") (pinfunction "1_1") (pintype "input"))
      (node (ref "R29") (pin "1") (pinfunction "1_1") (pintype "input"))
      (node (ref "R35") (pin "1") (pinfunction "1_1") (pintype "input"))
      (node (ref "R41") (pin "1") (pinfunction "1_1") (pintype "input"))
      (node (ref "R47") (pin "1") (pinfunction "1_1") (pintype "input"))
      (node (ref "U11") (pin "2") (pinfunction "E_2") (pintype "input"))
      (node (ref "U12") (pin "1") (pinfunction "1_1") (pintype "unspecified"))
      (node (ref "U13") (pin "3") (pinfunction "EM_3") (pintype "unspecified"))
      (node (ref "U14") (pin "2") (pinfunction "E_2") (pintype "input"))
      (node (ref "U16") (pin "3") (pinfunction "EM_3") (pintype "unspecified"))
      (node (ref "U17") (pin "1") (pinfunction "S_1") (pintype "unspecified"))
      (node (ref "U17") (pin "2") (pinfunction "S_2") (pintype "unspecified"))
      (node (ref "U17") (pin "3") (pinfunction "S_3") (pintype "unspecified"))
      (node (ref "U18") (pin "2") (pinfunction "E_2") (pintype "input"))
      (node (ref "U20") (pin "3") (pinfunction "EM_3") (pintype "unspecified"))
      (node (ref "U21") (pin "1") (pinfunction "S_1") (pintype "unspecified"))
      (node (ref "U21") (pin "2") (pinfunction "S_2") (pintype "unspecified"))
      (node (ref "U21") (pin "3") (pinfunction "S_3") (pintype "unspecified"))
      (node (ref "U22") (pin "2") (pinfunction "E_2") (pintype "input"))
      (node (ref "U24") (pin "3") (pinfunction "EM_3") (pintype "unspecified"))
      (node (ref "U25") (pin "1") (pinfunction "S_1") (pintype "unspecified"))
      (node (ref "U25") (pin "2") (pinfunction "S_2") (pintype "unspecified"))
      (node (ref "U25") (pin "3") (pinfunction "S_3") (pintype "unspecified"))
      (node (ref "U26") (pin "2") (pinfunction "E_2") (pintype "input"))
      (node (ref "U28") (pin "3") (pinfunction "EM_3") (pintype "unspecified"))
      (node (ref "U29") (pin "1") (pinfunction "S_1") (pintype "unspecified"))
      (node (ref "U29") (pin "2") (pinfunction "S_2") (pintype "unspecified"))
      (node (ref "U29") (pin "3") (pinfunction "S_3") (pintype "unspecified"))
      (node (ref "U30") (pin "2") (pinfunction "E_2") (pintype "input"))
      (node (ref "U32") (pin "3") (pinfunction "EM_3") (pintype "unspecified"))
      (node (ref "U33") (pin "1") (pinfunction "S_1") (pintype "unspecified"))
      (node (ref "U33") (pin "2") (pinfunction "S_2") (pintype "unspecified"))
      (node (ref "U33") (pin "3") (pinfunction "S_3") (pintype "unspecified"))
      (node (ref "U34") (pin "2") (pinfunction "E_2") (pintype "input"))
      (node (ref "U36") (pin "3") (pinfunction "EM_3") (pintype "unspecified"))
      (node (ref "U37") (pin "1") (pinfunction "S_1") (pintype "unspecified"))
      (node (ref "U37") (pin "2") (pinfunction "S_2") (pintype "unspecified"))
      (node (ref "U37") (pin "3") (pinfunction "S_3") (pintype "unspecified"))
      (node (ref "U38") (pin "2") (pinfunction "E_2") (pintype "input"))
      (node (ref "ZD1") (pin "1") (pinfunction "A_1") (pintype "unspecified"))
      (node (ref "ZD2") (pin "1") (pinfunction "A_1") (pintype "unspecified"))
      (node (ref "ZD3") (pin "1") (pinfunction "A_1") (pintype "unspecified"))
      (node (ref "ZD4") (pin "1") (pinfunction "A_1") (pintype "unspecified"))
      (node (ref "ZD5") (pin "1") (pinfunction "A_1") (pintype "unspecified"))
      (node (ref "ZD6") (pin "1") (pinfunction "A_1") (pintype "unspecified"))
    )
    (net (code "5") (name "EN") (class "Default")
      (node (ref "H10") (pin "2") (pinfunction "2_2") (pintype "unspecified"))
      (node (ref "H3") (pin "2") (pinfunction "2_2") (pintype "unspecified"))
      (node (ref "R68") (pin "1") (pinfunction "1_1") (pintype "input"))
    )
    (net (code "6") (name "EN_OUT") (class "Default")
      (node (ref "U14") (pin "3") (pinfunction "C_3") (pintype "input"))
    )
    (net (code "7") (name "GATE1") (class "Default")
      (node (ref "R15") (pin "2") (pinfunction "2_2") (pintype "input"))
      (node (ref "R17") (pin "2") (pinfunction "2_2") (pintype "input"))
      (node (ref "U17") (pin "4") (pinfunction "G_4") (pintype "unspecified"))
      (node (ref "ZD1") (pin "2") (pinfunction "K_2") (pintype "unspecified"))
    )
    (net (code "8") (name "GATE2") (class "Default")
      (node (ref "R21") (pin "2") (pinfunction "2_2") (pintype "input"))
      (node (ref "R23") (pin "2") (pinfunction "2_2") (pintype "input"))
      (node (ref "U21") (pin "4") (pinfunction "G_4") (pintype "unspecified"))
      (node (ref "ZD2") (pin "2") (pinfunction "K_2") (pintype "unspecified"))
    )
    (net (code "9") (name "GATE3") (class "Default")
      (node (ref "R27") (pin "2") (pinfunction "2_2") (pintype "input"))
      (node (ref "R29") (pin "2") (pinfunction "2_2") (pintype "input"))
      (node (ref "U25") (pin "4") (pinfunction "G_4") (pintype "unspecified"))
      (node (ref "ZD3") (pin "2") (pinfunction "K_2") (pintype "unspecified"))
    )
    (net (code "10") (name "GATE4") (class "Default")
      (node (ref "R33") (pin "2") (pinfunction "2_2") (pintype "input"))
      (node (ref "R35") (pin "2") (pinfunction "2_2") (pintype "input"))
      (node (ref "U29") (pin "4") (pinfunction "G_4") (pintype "unspecified"))
      (node (ref "ZD4") (pin "2") (pinfunction "K_2") (pintype "unspecified"))
    )
    (net (code "11") (name "GATE5") (class "Default")
      (node (ref "R39") (pin "2") (pinfunction "2_2") (pintype "input"))
      (node (ref "R41") (pin "2") (pinfunction "2_2") (pintype "input"))
      (node (ref "U33") (pin "4") (pinfunction "G_4") (pintype "unspecified"))
      (node (ref "ZD5") (pin "2") (pinfunction "K_2") (pintype "unspecified"))
    )
    (net (code "12") (name "GATE6") (class "Default")
      (node (ref "R45") (pin "2") (pinfunction "2_2") (pintype "input"))
      (node (ref "R47") (pin "2") (pinfunction "2_2") (pintype "input"))
      (node (ref "U37") (pin "4") (pinfunction "G_4") (pintype "unspecified"))
      (node (ref "ZD6") (pin "2") (pinfunction "K_2") (pintype "unspecified"))
    )
    (net (code "13") (name "GND") (class "Default")
      (node (ref "C5") (pin "1") (pinfunction "1_1") (pintype "input"))
      (node (ref "C6") (pin "1") (pinfunction "1_1") (pintype "input"))
      (node (ref "C7") (pin "1") (pinfunction "1_1") (pintype "input"))
      (node (ref "C8") (pin "1") (pinfunction "1_1") (pintype "input"))
      (node (ref "H10") (pin "1") (pinfunction "1_1") (pintype "unspecified"))
      (node (ref "H3") (pin "1") (pinfunction "1_1") (pintype "unspecified"))
      (node (ref "U1") (pin "2") (pinfunction "2_2") (pintype "unspecified"))
      (node (ref "U2") (pin "3") (pinfunction "EM_3") (pintype "unspecified"))
      (node (ref "U39") (pin "2") (pinfunction "E_2") (pintype "input"))
      (node (ref "U40") (pin "2") (pinfunction "E_2") (pintype "input"))
      (node (ref "U41") (pin "2") (pinfunction "E_2") (pintype "input"))
      (node (ref "U42") (pin "2") (pinfunction "E_2") (pintype "input"))
      (node (ref "U43") (pin "2") (pinfunction "E_2") (pintype "input"))
      (node (ref "U44") (pin "2") (pinfunction "E_2") (pintype "input"))
      (node (ref "U45") (pin "1") (pinfunction "GND_1") (pintype "unspecified"))
      (node (ref "U47") (pin "1") (pinfunction "GND_1") (pintype "unspecified"))
      (node (ref "U48") (pin "2") (pinfunction "E_2") (pintype "input"))
      (node (ref "U5") (pin "3") (pinfunction "EM_3") (pintype "unspecified"))
      (node (ref "U8") (pin "3") (pinfunction "EM_3") (pintype "unspecified"))
    )
    (net (code "14") (name "L1-OUT-") (class "Default")
      (node (ref "D5") (pin "2") (pinfunction "A_2") (pintype "unspecified"))
      (node (ref "LED10") (pin "1") (pinfunction "C_1") (pintype "input"))
      (node (ref "U15") (pin "2") (pinfunction "2_2") (pintype "unspecified"))
      (node (ref "U17") (pin "5") (pinfunction "D_5") (pintype "unspecified"))
      (node (ref "U17") (pin "6") (pinfunction "D_6") (pintype "unspecified"))
      (node (ref "U17") (pin "7") (pinfunction "D_7") (pintype "unspecified"))
      (node (ref "U17") (pin "8") (pinfunction "D_8") (pintype "unspecified"))
    )
    (net (code "15") (name "L1-VIN+") (class "Default")
      (node (ref "D1") (pin "2") (pinfunction "2_2") (pintype "unspecified"))
      (node (ref "U3") (pin "2") (pinfunction "A_2") (pintype "unspecified"))
      (node (ref "U4") (pin "1") (pinfunction "1_1") (pintype "unspecified"))
    )
    (net (code "16") (name "L1-VIN-") (class "Default")
      (node (ref "C1") (pin "1") (pinfunction "1_1") (pintype "input"))
      (node (ref "D1") (pin "1") (pinfunction "1_1") (pintype "unspecified"))
      (node (ref "U2") (pin "2") (pinfunction "C_2") (pintype "unspecified"))
      (node (ref "U4") (pin "2") (pinfunction "2_2") (pintype "unspecified"))
    )
    (net (code "17") (name "L2-OUT-") (class "Default")
      (node (ref "D6") (pin "2") (pinfunction "A_2") (pintype "unspecified"))
      (node (ref "LED11") (pin "1") (pinfunction "C_1") (pintype "input"))
      (node (ref "U19") (pin "2") (pinfunction "2_2") (pintype "unspecified"))
      (node (ref "U21") (pin "5") (pinfunction "D_5") (pintype "unspecified"))
      (node (ref "U21") (pin "6") (pinfunction "D_6") (pintype "unspecified"))
      (node (ref "U21") (pin "7") (pinfunction "D_7") (pintype "unspecified"))
      (node (ref "U21") (pin "8") (pinfunction "D_8") (pintype "unspecified"))
    )
    (net (code "18") (name "L2-VIN+") (class "Default")
      (node (ref "D2") (pin "2") (pinfunction "2_2") (pintype "unspecified"))
      (node (ref "U6") (pin "2") (pinfunction "A_2") (pintype "unspecified"))
      (node (ref "U7") (pin "1") (pinfunction "1_1") (pintype "unspecified"))
    )
    (net (code "19") (name "L2-VIN-") (class "Default")
      (node (ref "C2") (pin "1") (pinfunction "1_1") (pintype "input"))
      (node (ref "D2") (pin "1") (pinfunction "1_1") (pintype "unspecified"))
      (node (ref "U5") (pin "2") (pinfunction "C_2") (pintype "unspecified"))
      (node (ref "U7") (pin "2") (pinfunction "2_2") (pintype "unspecified"))
    )
    (net (code "20") (name "L3-OUT-") (class "Default")
      (node (ref "D7") (pin "2") (pinfunction "A_2") (pintype "unspecified"))
      (node (ref "LED13") (pin "1") (pinfunction "C_1") (pintype "input"))
      (node (ref "U23") (pin "2") (pinfunction "2_2") (pintype "unspecified"))
      (node (ref "U25") (pin "5") (pinfunction "D_5") (pintype "unspecified"))
      (node (ref "U25") (pin "6") (pinfunction "D_6") (pintype "unspecified"))
      (node (ref "U25") (pin "7") (pinfunction "D_7") (pintype "unspecified"))
      (node (ref "U25") (pin "8") (pinfunction "D_8") (pintype "unspecified"))
    )
    (net (code "21") (name "L3-VIN+") (class "Default")
      (node (ref "D3") (pin "2") (pinfunction "2_2") (pintype "unspecified"))
      (node (ref "U10") (pin "1") (pinfunction "1_1") (pintype "unspecified"))
      (node (ref "U9") (pin "2") (pinfunction "A_2") (pintype "unspecified"))
    )
    (net (code "22") (name "L3-VIN-") (class "Default")
      (node (ref "C3") (pin "1") (pinfunction "1_1") (pintype "input"))
      (node (ref "D3") (pin "1") (pinfunction "1_1") (pintype "unspecified"))
      (node (ref "U10") (pin "2") (pinfunction "2_2") (pintype "unspecified"))
      (node (ref "U8") (pin "2") (pinfunction "C_2") (pintype "unspecified"))
    )
    (net (code "23") (name "L4-OUT-") (class "Default")
      (node (ref "D8") (pin "2") (pinfunction "A_2") (pintype "unspecified"))
      (node (ref "LED14") (pin "1") (pinfunction "C_1") (pintype "input"))
      (node (ref "U27") (pin "2") (pinfunction "2_2") (pintype "unspecified"))
      (node (ref "U29") (pin "5") (pinfunction "D_5") (pintype "unspecified"))
      (node (ref "U29") (pin "6") (pinfunction "D_6") (pintype "unspecified"))
      (node (ref "U29") (pin "7") (pinfunction "D_7") (pintype "unspecified"))
      (node (ref "U29") (pin "8") (pinfunction "D_8") (pintype "unspecified"))
    )
    (net (code "24") (name "L5-OUT-") (class "Default")
      (node (ref "D9") (pin "2") (pinfunction "A_2") (pintype "unspecified"))
      (node (ref "LED15") (pin "1") (pinfunction "C_1") (pintype "input"))
      (node (ref "U31") (pin "2") (pinfunction "2_2") (pintype "unspecified"))
      (node (ref "U33") (pin "5") (pinfunction "D_5") (pintype "unspecified"))
      (node (ref "U33") (pin "6") (pinfunction "D_6") (pintype "unspecified"))
      (node (ref "U33") (pin "7") (pinfunction "D_7") (pintype "unspecified"))
      (node (ref "U33") (pin "8") (pinfunction "D_8") (pintype "unspecified"))
    )
    (net (code "25") (name "L6-OUT-") (class "Default")
      (node (ref "D10") (pin "2") (pinfunction "A_2") (pintype "unspecified"))
      (node (ref "LED16") (pin "1") (pinfunction "C_1") (pintype "input"))
      (node (ref "U35") (pin "2") (pinfunction "2_2") (pintype "unspecified"))
      (node (ref "U37") (pin "5") (pinfunction "D_5") (pintype "unspecified"))
      (node (ref "U37") (pin "6") (pinfunction "D_6") (pintype "unspecified"))
      (node (ref "U37") (pin "7") (pinfunction "D_7") (pintype "unspecified"))
      (node (ref "U37") (pin "8") (pinfunction "D_8") (pintype "unspecified"))
    )
    (net (code "26") (name "LINE_1") (class "Default")
      (node (ref "H10") (pin "3") (pinfunction "3_3") (pintype "unspecified"))
      (node (ref "H3") (pin "3") (pinfunction "3_3") (pintype "unspecified"))
      (node (ref "R62") (pin "1") (pinfunction "1_1") (pintype "input"))
    )
    (net (code "27") (name "LINE_2") (class "Default")
      (node (ref "H10") (pin "4") (pinfunction "4_4") (pintype "unspecified"))
      (node (ref "H3") (pin "4") (pinfunction "4_4") (pintype "unspecified"))
      (node (ref "R63") (pin "1") (pinfunction "1_1") (pintype "input"))
    )
    (net (code "28") (name "LINE_3") (class "Default")
      (node (ref "H10") (pin "5") (pinfunction "5_5") (pintype "unspecified"))
      (node (ref "H3") (pin "5") (pinfunction "5_5") (pintype "unspecified"))
      (node (ref "R64") (pin "1") (pinfunction "1_1") (pintype "input"))
    )
    (net (code "29") (name "LINE_4") (class "Default")
      (node (ref "H10") (pin "6") (pinfunction "6_6") (pintype "unspecified"))
      (node (ref "H3") (pin "6") (pinfunction "6_6") (pintype "unspecified"))
      (node (ref "R65") (pin "1") (pinfunction "1_1") (pintype "input"))
    )
    (net (code "30") (name "LINE_5") (class "Default")
      (node (ref "H10") (pin "7") (pinfunction "7_7") (pintype "unspecified"))
      (node (ref "H3") (pin "7") (pinfunction "7_7") (pintype "unspecified"))
      (node (ref "R66") (pin "1") (pinfunction "1_1") (pintype "input"))
    )
    (net (code "31") (name "LINE_6") (class "Default")
      (node (ref "H10") (pin "8") (pinfunction "8_8") (pintype "unspecified"))
      (node (ref "H3") (pin "8") (pinfunction "8_8") (pintype "unspecified"))
      (node (ref "R67") (pin "1") (pinfunction "1_1") (pintype "input"))
    )
    (net (code "32") (name "LINE_PC817_2_1") (class "Default")
      (node (ref "R53") (pin "2") (pinfunction "2_2") (pintype "input"))
      (node (ref "U16") (pin "2") (pinfunction "C_2") (pintype "unspecified"))
      (node (ref "U39") (pin "3") (pinfunction "C_3") (pintype "input"))
    )
    (net (code "33") (name "LINE_PC817_2_2") (class "Default")
      (node (ref "R52") (pin "2") (pinfunction "2_2") (pintype "input"))
      (node (ref "U20") (pin "2") (pinfunction "C_2") (pintype "unspecified"))
      (node (ref "U40") (pin "3") (pinfunction "C_3") (pintype "input"))
    )
    (net (code "34") (name "LINE_PC817_2_3") (class "Default")
      (node (ref "R51") (pin "2") (pinfunction "2_2") (pintype "input"))
      (node (ref "U24") (pin "2") (pinfunction "C_2") (pintype "unspecified"))
      (node (ref "U41") (pin "3") (pinfunction "C_3") (pintype "input"))
    )
    (net (code "35") (name "LINE_PC817_2_4") (class "Default")
      (node (ref "R50") (pin "2") (pinfunction "2_2") (pintype "input"))
      (node (ref "U28") (pin "2") (pinfunction "C_2") (pintype "unspecified"))
      (node (ref "U42") (pin "3") (pinfunction "C_3") (pintype "input"))
    )
    (net (code "36") (name "LINE_PC817_2_5") (class "Default")
      (node (ref "R49") (pin "2") (pinfunction "2_2") (pintype "input"))
      (node (ref "U32") (pin "2") (pinfunction "C_2") (pintype "unspecified"))
      (node (ref "U43") (pin "3") (pinfunction "C_3") (pintype "input"))
    )
    (net (code "37") (name "LINE_PC817_2_6") (class "Default")
      (node (ref "R48") (pin "2") (pinfunction "2_2") (pintype "input"))
      (node (ref "U36") (pin "2") (pinfunction "C_2") (pintype "unspecified"))
      (node (ref "U44") (pin "3") (pinfunction "C_3") (pintype "input"))
    )
    (net (code "38") (name "Net-(H2-Pad2)") (class "Default")
      (node (ref "H2") (pin "2") (pinfunction "2_2") (pintype "input"))
      (node (ref "R11") (pin "2") (pinfunction "2_2") (pintype "input"))
    )
    (net (code "39") (name "Net-(H4-Pad2)") (class "Default")
      (node (ref "H4") (pin "2") (pinfunction "2_2") (pintype "input"))
      (node (ref "R15") (pin "1") (pinfunction "1_1") (pintype "input"))
    )
    (net (code "40") (name "Net-(H5-Pad2)") (class "Default")
      (node (ref "H5") (pin "2") (pinfunction "2_2") (pintype "input"))
      (node (ref "R21") (pin "1") (pinfunction "1_1") (pintype "input"))
    )
    (net (code "41") (name "Net-(H6-Pad2)") (class "Default")
      (node (ref "H6") (pin "2") (pinfunction "2_2") (pintype "input"))
      (node (ref "R27") (pin "1") (pinfunction "1_1") (pintype "input"))
    )
    (net (code "42") (name "Net-(H7-Pad2)") (class "Default")
      (node (ref "H7") (pin "2") (pinfunction "2_2") (pintype "input"))
      (node (ref "R33") (pin "1") (pinfunction "1_1") (pintype "input"))
    )
    (net (code "43") (name "Net-(H8-Pad2)") (class "Default")
      (node (ref "H8") (pin "2") (pinfunction "2_2") (pintype "input"))
      (node (ref "R39") (pin "1") (pinfunction "1_1") (pintype "input"))
    )
    (net (code "44") (name "Net-(H9-Pad2)") (class "Default")
      (node (ref "H9") (pin "2") (pinfunction "2_2") (pintype "input"))
      (node (ref "R45") (pin "1") (pinfunction "1_1") (pintype "input"))
    )
    (net (code "45") (name "Net-(LED1-A)") (class "Default")
      (node (ref "LED1") (pin "2") (pinfunction "A_2") (pintype "input"))
      (node (ref "R2") (pin "1") (pinfunction "1_1") (pintype "input"))
    )
    (net (code "46") (name "Net-(LED1-C)") (class "Default")
      (node (ref "LED1") (pin "1") (pinfunction "C_1") (pintype "input"))
      (node (ref "U2") (pin "1") (pinfunction "A_1") (pintype "unspecified"))
    )
    (net (code "47") (name "Net-(LED2-A)") (class "Default")
      (node (ref "LED2") (pin "2") (pinfunction "A_2") (pintype "input"))
      (node (ref "R4") (pin "1") (pinfunction "1_1") (pintype "input"))
    )
    (net (code "48") (name "Net-(LED2-C)") (class "Default")
      (node (ref "LED2") (pin "1") (pinfunction "C_1") (pintype "input"))
      (node (ref "U5") (pin "1") (pinfunction "A_1") (pintype "unspecified"))
    )
    (net (code "49") (name "Net-(LED3-A)") (class "Default")
      (node (ref "LED3") (pin "2") (pinfunction "A_2") (pintype "input"))
      (node (ref "R6") (pin "1") (pinfunction "1_1") (pintype "input"))
    )
    (net (code "50") (name "Net-(LED3-C)") (class "Default")
      (node (ref "LED3") (pin "1") (pinfunction "C_1") (pintype "input"))
      (node (ref "U8") (pin "1") (pinfunction "A_1") (pintype "unspecified"))
    )
    (net (code "51") (name "Net-(LED4-C)") (class "Default")
      (node (ref "LED4") (pin "1") (pinfunction "C_1") (pintype "input"))
      (node (ref "R48") (pin "1") (pinfunction "1_1") (pintype "input"))
    )
    (net (code "52") (name "Net-(LED5-C)") (class "Default")
      (node (ref "LED5") (pin "1") (pinfunction "C_1") (pintype "input"))
      (node (ref "R49") (pin "1") (pinfunction "1_1") (pintype "input"))
    )
    (net (code "53") (name "Net-(LED6-C)") (class "Default")
      (node (ref "LED6") (pin "1") (pinfunction "C_1") (pintype "input"))
      (node (ref "R50") (pin "1") (pinfunction "1_1") (pintype "input"))
    )
    (net (code "54") (name "Net-(LED7-C)") (class "Default")
      (node (ref "LED7") (pin "1") (pinfunction "C_1") (pintype "input"))
      (node (ref "R51") (pin "1") (pinfunction "1_1") (pintype "input"))
    )
    (net (code "55") (name "Net-(LED8-C)") (class "Default")
      (node (ref "LED8") (pin "1") (pinfunction "C_1") (pintype "input"))
      (node (ref "R52") (pin "1") (pinfunction "1_1") (pintype "input"))
    )
    (net (code "56") (name "Net-(LED9-C)") (class "Default")
      (node (ref "LED9") (pin "1") (pinfunction "C_1") (pintype "input"))
      (node (ref "R53") (pin "1") (pinfunction "1_1") (pintype "input"))
    )
    (net (code "57") (name "Net-(LED10-A)") (class "Default")
      (node (ref "LED10") (pin "2") (pinfunction "A_2") (pintype "input"))
      (node (ref "R54") (pin "2") (pinfunction "2_2") (pintype "input"))
    )
    (net (code "58") (name "Net-(LED11-A)") (class "Default")
      (node (ref "LED11") (pin "2") (pinfunction "A_2") (pintype "input"))
      (node (ref "R55") (pin "2") (pinfunction "2_2") (pintype "input"))
    )
    (net (code "59") (name "Net-(LED13-A)") (class "Default")
      (node (ref "LED13") (pin "2") (pinfunction "A_2") (pintype "input"))
      (node (ref "R57") (pin "2") (pinfunction "2_2") (pintype "input"))
    )
    (net (code "60") (name "Net-(LED14-A)") (class "Default")
      (node (ref "LED14") (pin "2") (pinfunction "A_2") (pintype "input"))
      (node (ref "R58") (pin "2") (pinfunction "2_2") (pintype "input"))
    )
    (net (code "61") (name "Net-(LED15-A)") (class "Default")
      (node (ref "LED15") (pin "2") (pinfunction "A_2") (pintype "input"))
      (node (ref "R59") (pin "2") (pinfunction "2_2") (pintype "input"))
    )
    (net (code "62") (name "Net-(LED16-A)") (class "Default")
      (node (ref "LED16") (pin "2") (pinfunction "A_2") (pintype "input"))
      (node (ref "R60") (pin "2") (pinfunction "2_2") (pintype "input"))
    )
    (net (code "63") (name "Net-(LED17-C)") (class "Default")
      (node (ref "LED17") (pin "1") (pinfunction "C_1") (pintype "input"))
      (node (ref "R69") (pin "1") (pinfunction "1_1") (pintype "input"))
    )
    (net (code "64") (name "Net-(U2-COL)") (class "Default")
      (node (ref "H1") (pin "3") (pinfunction "3_3") (pintype "input"))
      (node (ref "R1") (pin "2") (pinfunction "2_2") (pintype "input"))
      (node (ref "U2") (pin "4") (pinfunction "COL_4") (pintype "unspecified"))
    )
    (net (code "65") (name "Net-(U3-K)") (class "Default")
      (node (ref "C1") (pin "2") (pinfunction "2_2") (pintype "input"))
      (node (ref "R2") (pin "2") (pinfunction "2_2") (pintype "input"))
      (node (ref "U3") (pin "1") (pinfunction "K_1") (pintype "unspecified"))
    )
    (net (code "66") (name "Net-(U5-COL)") (class "Default")
      (node (ref "H1") (pin "2") (pinfunction "2_2") (pintype "input"))
      (node (ref "R3") (pin "2") (pinfunction "2_2") (pintype "input"))
      (node (ref "U5") (pin "4") (pinfunction "COL_4") (pintype "unspecified"))
    )
    (net (code "67") (name "Net-(U6-K)") (class "Default")
      (node (ref "C2") (pin "2") (pinfunction "2_2") (pintype "input"))
      (node (ref "R4") (pin "2") (pinfunction "2_2") (pintype "input"))
      (node (ref "U6") (pin "1") (pinfunction "K_1") (pintype "unspecified"))
    )
    (net (code "68") (name "Net-(U8-COL)") (class "Default")
      (node (ref "H1") (pin "1") (pinfunction "1_1") (pintype "input"))
      (node (ref "R5") (pin "2") (pinfunction "2_2") (pintype "input"))
      (node (ref "U8") (pin "4") (pinfunction "COL_4") (pintype "unspecified"))
    )
    (net (code "69") (name "Net-(U9-K)") (class "Default")
      (node (ref "C3") (pin "2") (pinfunction "2_2") (pintype "input"))
      (node (ref "R6") (pin "2") (pinfunction "2_2") (pintype "input"))
      (node (ref "U9") (pin "1") (pinfunction "K_1") (pintype "unspecified"))
    )
    (net (code "70") (name "Net-(U11-B)") (class "Default")
      (node (ref "R9") (pin "2") (pinfunction "2_2") (pintype "input"))
      (node (ref "U11") (pin "1") (pinfunction "B_1") (pintype "input"))
    )
    (net (code "71") (name "Net-(U11-C)") (class "Default")
      (node (ref "H2") (pin "1") (pinfunction "1_1") (pintype "input"))
      (node (ref "R7") (pin "1") (pinfunction "1_1") (pintype "input"))
      (node (ref "U11") (pin "3") (pinfunction "C_3") (pintype "input"))
    )
    (net (code "72") (name "Net-(U13-A)") (class "Default")
      (node (ref "R70") (pin "2") (pinfunction "2_2") (pintype "input"))
      (node (ref "U13") (pin "1") (pinfunction "A_1") (pintype "unspecified"))
    )
    (net (code "73") (name "Net-(U13-C)") (class "Default")
      (node (ref "R69") (pin "2") (pinfunction "2_2") (pintype "input"))
      (node (ref "U13") (pin "2") (pinfunction "C_2") (pintype "unspecified"))
      (node (ref "U48") (pin "3") (pinfunction "C_3") (pintype "input"))
    )
    (net (code "74") (name "Net-(U13-COL)") (class "Default")
      (node (ref "H2") (pin "3") (pinfunction "3_3") (pintype "input"))
      (node (ref "R8") (pin "1") (pinfunction "1_1") (pintype "input"))
      (node (ref "R9") (pin "1") (pinfunction "1_1") (pintype "input"))
      (node (ref "U13") (pin "4") (pinfunction "COL_4") (pintype "unspecified"))
    )
    (net (code "75") (name "Net-(U14-B)") (class "Default")
      (node (ref "R11") (pin "1") (pinfunction "1_1") (pintype "input"))
      (node (ref "U14") (pin "1") (pinfunction "B_1") (pintype "input"))
    )
    (net (code "76") (name "Net-(U16-A)") (class "Default")
      (node (ref "R14") (pin "2") (pinfunction "2_2") (pintype "input"))
      (node (ref "U16") (pin "1") (pinfunction "A_1") (pintype "unspecified"))
    )
    (net (code "77") (name "Net-(U16-COL)") (class "Default")
      (node (ref "H4") (pin "3") (pinfunction "3_3") (pintype "input"))
      (node (ref "R12") (pin "1") (pinfunction "1_1") (pintype "input"))
      (node (ref "R16") (pin "2") (pinfunction "2_2") (pintype "input"))
      (node (ref "U16") (pin "4") (pinfunction "COL_4") (pintype "unspecified"))
    )
    (net (code "78") (name "Net-(U18-B)") (class "Default")
      (node (ref "R16") (pin "1") (pinfunction "1_1") (pintype "input"))
      (node (ref "U18") (pin "1") (pinfunction "B_1") (pintype "input"))
    )
    (net (code "79") (name "Net-(U18-C)") (class "Default")
      (node (ref "H4") (pin "1") (pinfunction "1_1") (pintype "input"))
      (node (ref "R13") (pin "1") (pinfunction "1_1") (pintype "input"))
      (node (ref "U18") (pin "3") (pinfunction "C_3") (pintype "input"))
    )
    (net (code "80") (name "Net-(U20-A)") (class "Default")
      (node (ref "R20") (pin "2") (pinfunction "2_2") (pintype "input"))
      (node (ref "U20") (pin "1") (pinfunction "A_1") (pintype "unspecified"))
    )
    (net (code "81") (name "Net-(U20-COL)") (class "Default")
      (node (ref "H5") (pin "3") (pinfunction "3_3") (pintype "input"))
      (node (ref "R18") (pin "1") (pinfunction "1_1") (pintype "input"))
      (node (ref "R22") (pin "2") (pinfunction "2_2") (pintype "input"))
      (node (ref "U20") (pin "4") (pinfunction "COL_4") (pintype "unspecified"))
    )
    (net (code "82") (name "Net-(U22-B)") (class "Default")
      (node (ref "R22") (pin "1") (pinfunction "1_1") (pintype "input"))
      (node (ref "U22") (pin "1") (pinfunction "B_1") (pintype "input"))
    )
    (net (code "83") (name "Net-(U22-C)") (class "Default")
      (node (ref "H5") (pin "1") (pinfunction "1_1") (pintype "input"))
      (node (ref "R19") (pin "1") (pinfunction "1_1") (pintype "input"))
      (node (ref "U22") (pin "3") (pinfunction "C_3") (pintype "input"))
    )
    (net (code "84") (name "Net-(U24-A)") (class "Default")
      (node (ref "R26") (pin "2") (pinfunction "2_2") (pintype "input"))
      (node (ref "U24") (pin "1") (pinfunction "A_1") (pintype "unspecified"))
    )
    (net (code "85") (name "Net-(U24-COL)") (class "Default")
      (node (ref "H6") (pin "3") (pinfunction "3_3") (pintype "input"))
      (node (ref "R24") (pin "1") (pinfunction "1_1") (pintype "input"))
      (node (ref "R28") (pin "2") (pinfunction "2_2") (pintype "input"))
      (node (ref "U24") (pin "4") (pinfunction "COL_4") (pintype "unspecified"))
    )
    (net (code "86") (name "Net-(U26-B)") (class "Default")
      (node (ref "R28") (pin "1") (pinfunction "1_1") (pintype "input"))
      (node (ref "U26") (pin "1") (pinfunction "B_1") (pintype "input"))
    )
    (net (code "87") (name "Net-(U26-C)") (class "Default")
      (node (ref "H6") (pin "1") (pinfunction "1_1") (pintype "input"))
      (node (ref "R25") (pin "1") (pinfunction "1_1") (pintype "input"))
      (node (ref "U26") (pin "3") (pinfunction "C_3") (pintype "input"))
    )
    (net (code "88") (name "Net-(U28-A)") (class "Default")
      (node (ref "R32") (pin "2") (pinfunction "2_2") (pintype "input"))
      (node (ref "U28") (pin "1") (pinfunction "A_1") (pintype "unspecified"))
    )
    (net (code "89") (name "Net-(U28-COL)") (class "Default")
      (node (ref "H7") (pin "3") (pinfunction "3_3") (pintype "input"))
      (node (ref "R30") (pin "1") (pinfunction "1_1") (pintype "input"))
      (node (ref "R34") (pin "2") (pinfunction "2_2") (pintype "input"))
      (node (ref "U28") (pin "4") (pinfunction "COL_4") (pintype "unspecified"))
    )
    (net (code "90") (name "Net-(U30-B)") (class "Default")
      (node (ref "R34") (pin "1") (pinfunction "1_1") (pintype "input"))
      (node (ref "U30") (pin "1") (pinfunction "B_1") (pintype "input"))
    )
    (net (code "91") (name "Net-(U30-C)") (class "Default")
      (node (ref "H7") (pin "1") (pinfunction "1_1") (pintype "input"))
      (node (ref "R31") (pin "1") (pinfunction "1_1") (pintype "input"))
      (node (ref "U30") (pin "3") (pinfunction "C_3") (pintype "input"))
    )
    (net (code "92") (name "Net-(U32-A)") (class "Default")
      (node (ref "R38") (pin "2") (pinfunction "2_2") (pintype "input"))
      (node (ref "U32") (pin "1") (pinfunction "A_1") (pintype "unspecified"))
    )
    (net (code "93") (name "Net-(U32-COL)") (class "Default")
      (node (ref "H8") (pin "3") (pinfunction "3_3") (pintype "input"))
      (node (ref "R36") (pin "1") (pinfunction "1_1") (pintype "input"))
      (node (ref "R40") (pin "2") (pinfunction "2_2") (pintype "input"))
      (node (ref "U32") (pin "4") (pinfunction "COL_4") (pintype "unspecified"))
    )
    (net (code "94") (name "Net-(U34-B)") (class "Default")
      (node (ref "R40") (pin "1") (pinfunction "1_1") (pintype "input"))
      (node (ref "U34") (pin "1") (pinfunction "B_1") (pintype "input"))
    )
    (net (code "95") (name "Net-(U34-C)") (class "Default")
      (node (ref "H8") (pin "1") (pinfunction "1_1") (pintype "input"))
      (node (ref "R37") (pin "1") (pinfunction "1_1") (pintype "input"))
      (node (ref "U34") (pin "3") (pinfunction "C_3") (pintype "input"))
    )
    (net (code "96") (name "Net-(U36-A)") (class "Default")
      (node (ref "R44") (pin "2") (pinfunction "2_2") (pintype "input"))
      (node (ref "U36") (pin "1") (pinfunction "A_1") (pintype "unspecified"))
    )
    (net (code "97") (name "Net-(U36-COL)") (class "Default")
      (node (ref "H9") (pin "3") (pinfunction "3_3") (pintype "input"))
      (node (ref "R42") (pin "1") (pinfunction "1_1") (pintype "input"))
      (node (ref "R46") (pin "2") (pinfunction "2_2") (pintype "input"))
      (node (ref "U36") (pin "4") (pinfunction "COL_4") (pintype "unspecified"))
    )
    (net (code "98") (name "Net-(U38-B)") (class "Default")
      (node (ref "R46") (pin "1") (pinfunction "1_1") (pintype "input"))
      (node (ref "U38") (pin "1") (pinfunction "B_1") (pintype "input"))
    )
    (net (code "99") (name "Net-(U38-C)") (class "Default")
      (node (ref "H9") (pin "1") (pinfunction "1_1") (pintype "input"))
      (node (ref "R43") (pin "1") (pinfunction "1_1") (pintype "input"))
      (node (ref "U38") (pin "3") (pinfunction "C_3") (pintype "input"))
    )
    (net (code "100") (name "Net-(U39-B)") (class "Default")
      (node (ref "R62") (pin "2") (pinfunction "2_2") (pintype "input"))
      (node (ref "U39") (pin "1") (pinfunction "B_1") (pintype "input"))
    )
    (net (code "101") (name "Net-(U40-B)") (class "Default")
      (node (ref "R63") (pin "2") (pinfunction "2_2") (pintype "input"))
      (node (ref "U40") (pin "1") (pinfunction "B_1") (pintype "input"))
    )
    (net (code "102") (name "Net-(U41-B)") (class "Default")
      (node (ref "R64") (pin "2") (pinfunction "2_2") (pintype "input"))
      (node (ref "U41") (pin "1") (pinfunction "B_1") (pintype "input"))
    )
    (net (code "103") (name "Net-(U42-B)") (class "Default")
      (node (ref "R65") (pin "2") (pinfunction "2_2") (pintype "input"))
      (node (ref "U42") (pin "1") (pinfunction "B_1") (pintype "input"))
    )
    (net (code "104") (name "Net-(U43-B)") (class "Default")
      (node (ref "R66") (pin "2") (pinfunction "2_2") (pintype "input"))
      (node (ref "U43") (pin "1") (pinfunction "B_1") (pintype "input"))
    )
    (net (code "105") (name "Net-(U44-B)") (class "Default")
      (node (ref "R67") (pin "2") (pinfunction "2_2") (pintype "input"))
      (node (ref "U44") (pin "1") (pinfunction "B_1") (pintype "input"))
    )
    (net (code "106") (name "Net-(U48-B)") (class "Default")
      (node (ref "R68") (pin "2") (pinfunction "2_2") (pintype "input"))
      (node (ref "U48") (pin "1") (pinfunction "B_1") (pintype "input"))
    )
    (net (code "107") (name "VIN") (class "Default")
      (node (ref "C6") (pin "2") (pinfunction "2_2") (pintype "input"))
      (node (ref "C8") (pin "2") (pinfunction "2_2") (pintype "input"))
      (node (ref "U1") (pin "1") (pinfunction "1_1") (pintype "unspecified"))
      (node (ref "U45") (pin "3") (pinfunction "VIN_3") (pintype "unspecified"))
      (node (ref "U47") (pin "3") (pinfunction "VIN_3") (pintype "unspecified"))
    )
  )
)
